# uDJV_board_2_v1_1.net
KiCad netlist of a schematic drawn in EAGLE
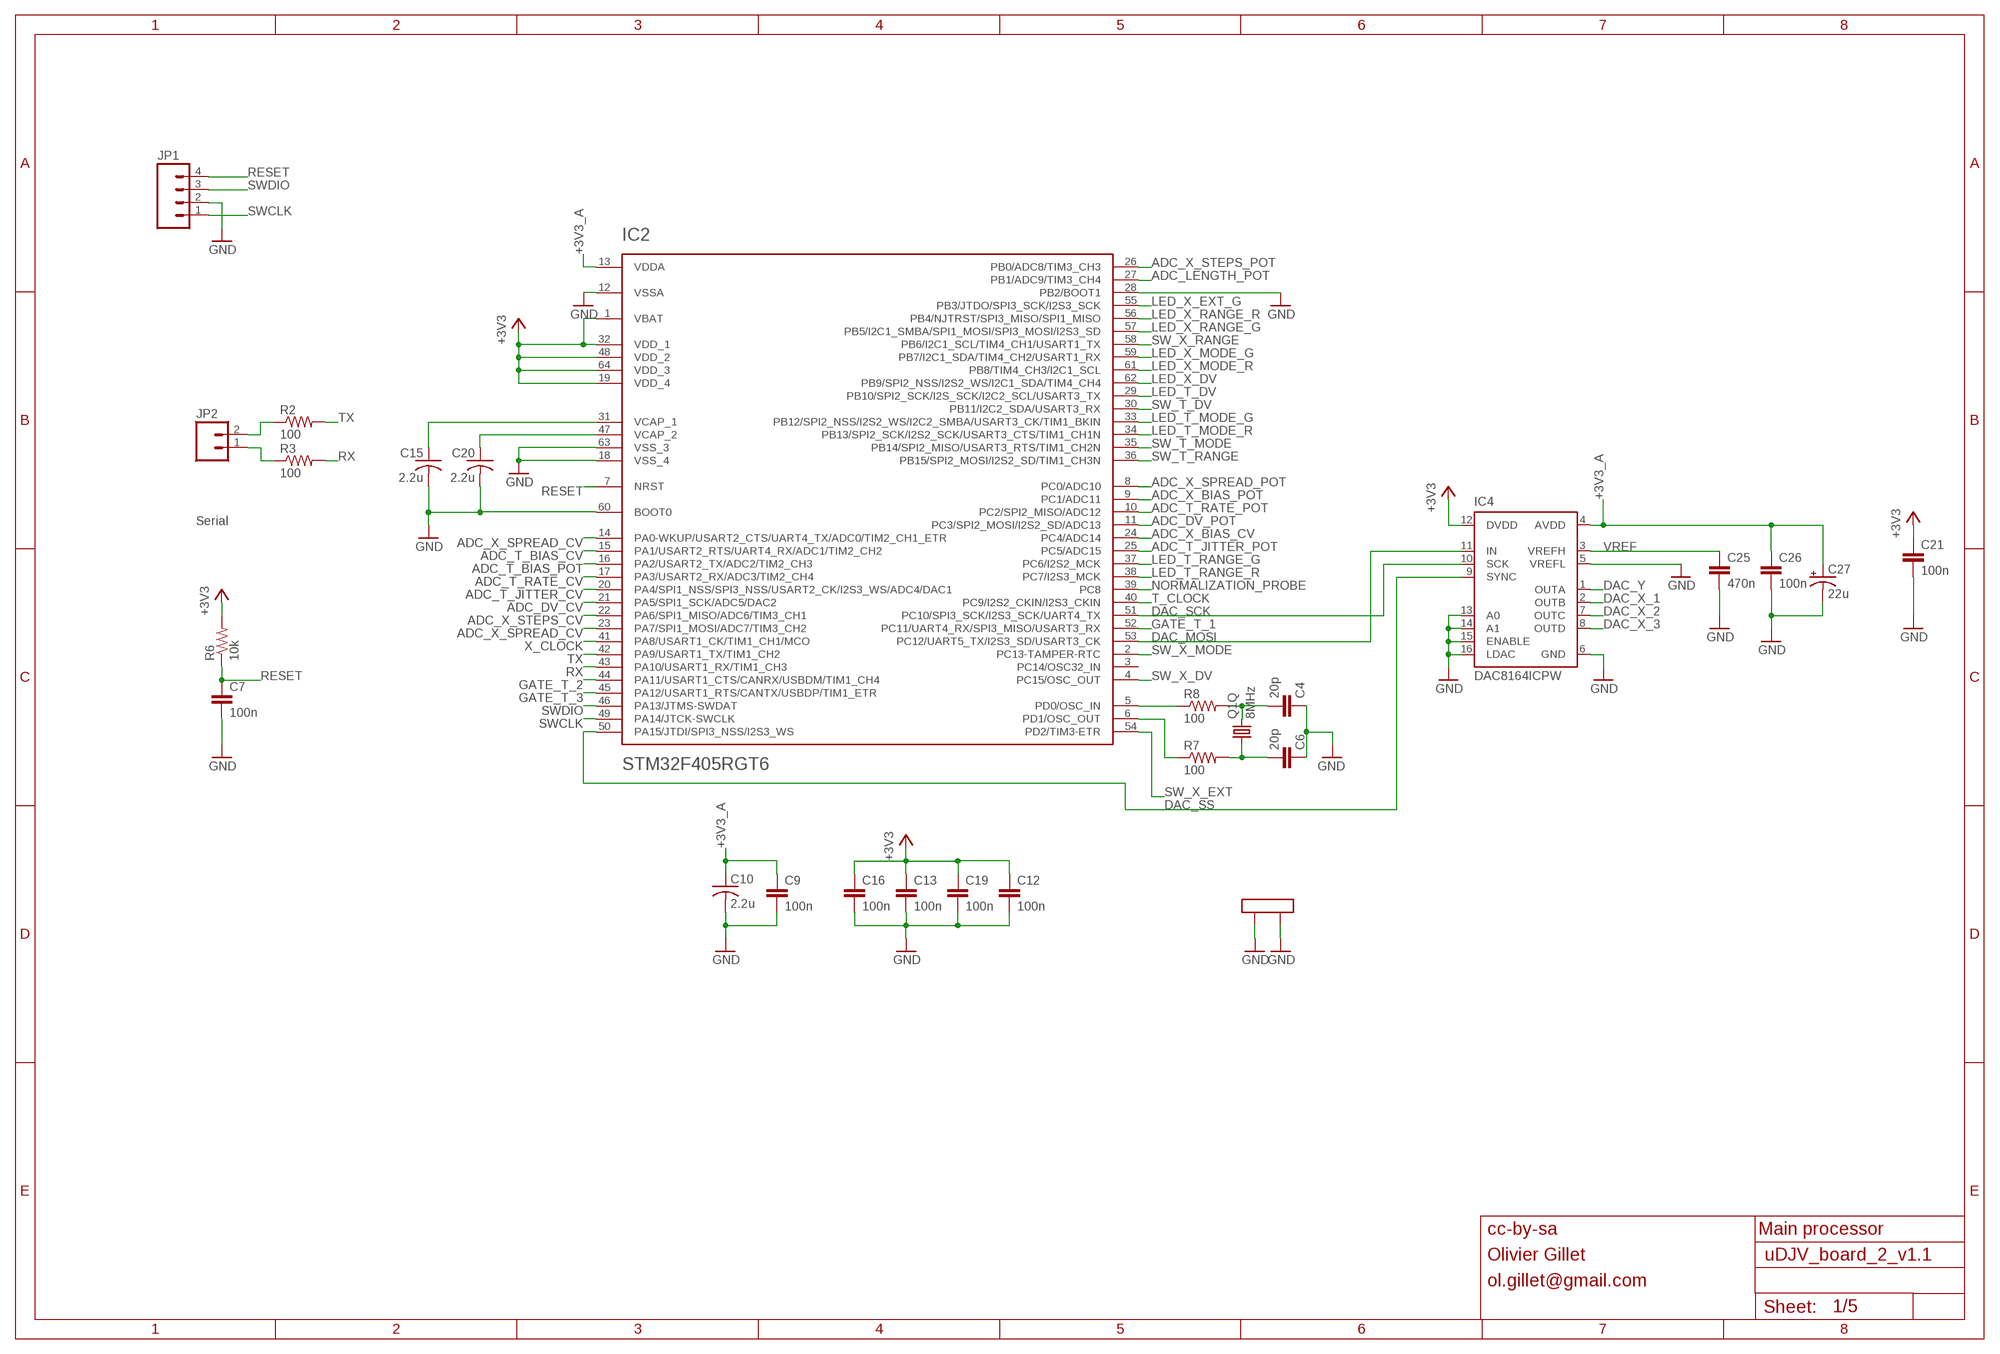
[diagram p0: schematic, sheet 1]
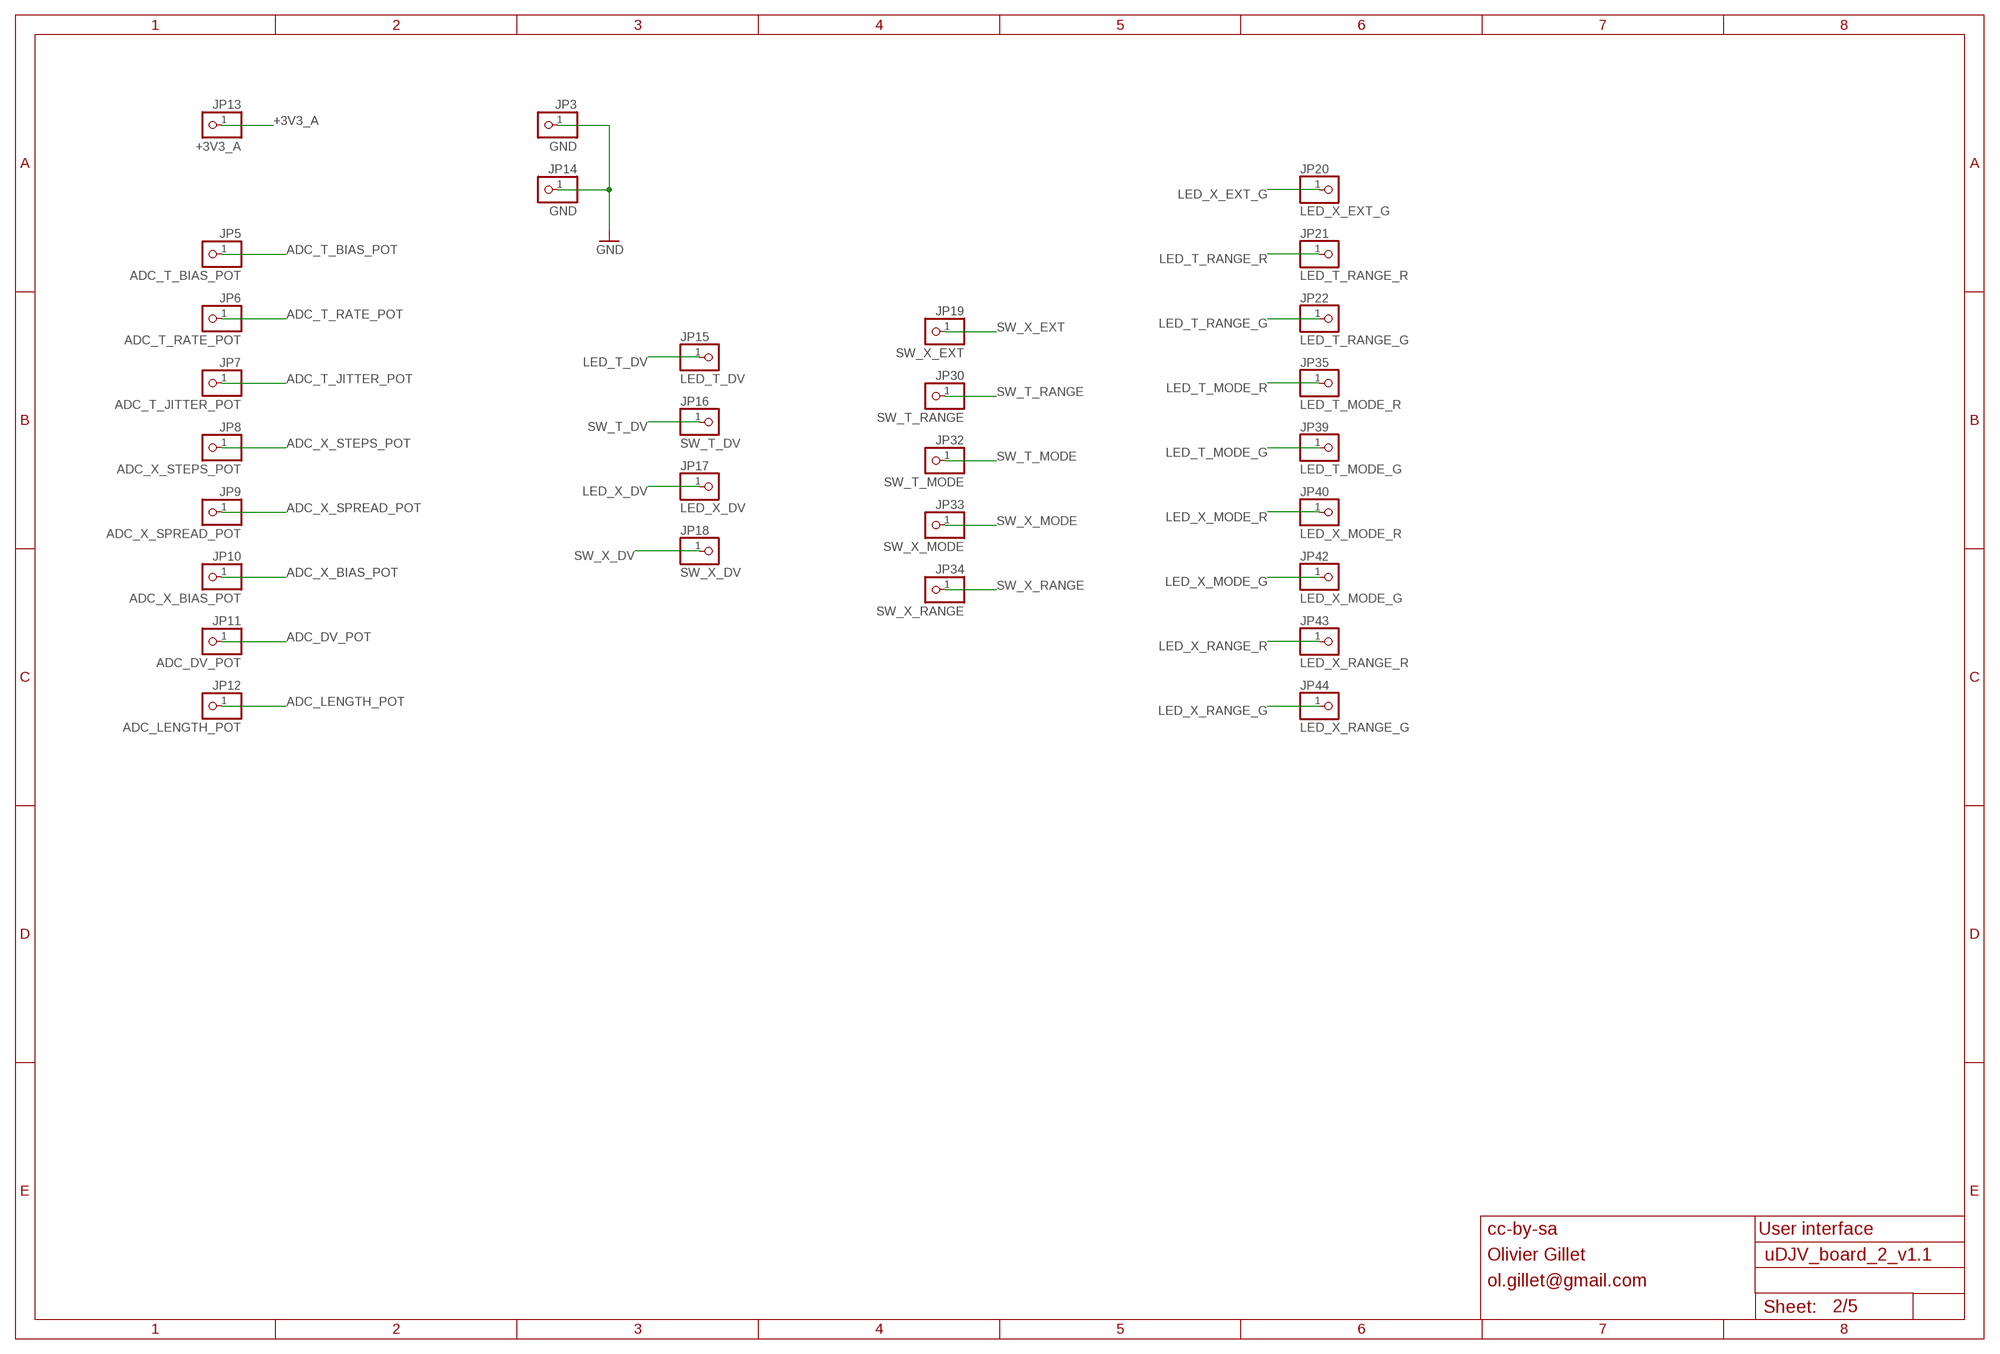
[diagram p1: schematic, sheet 2]
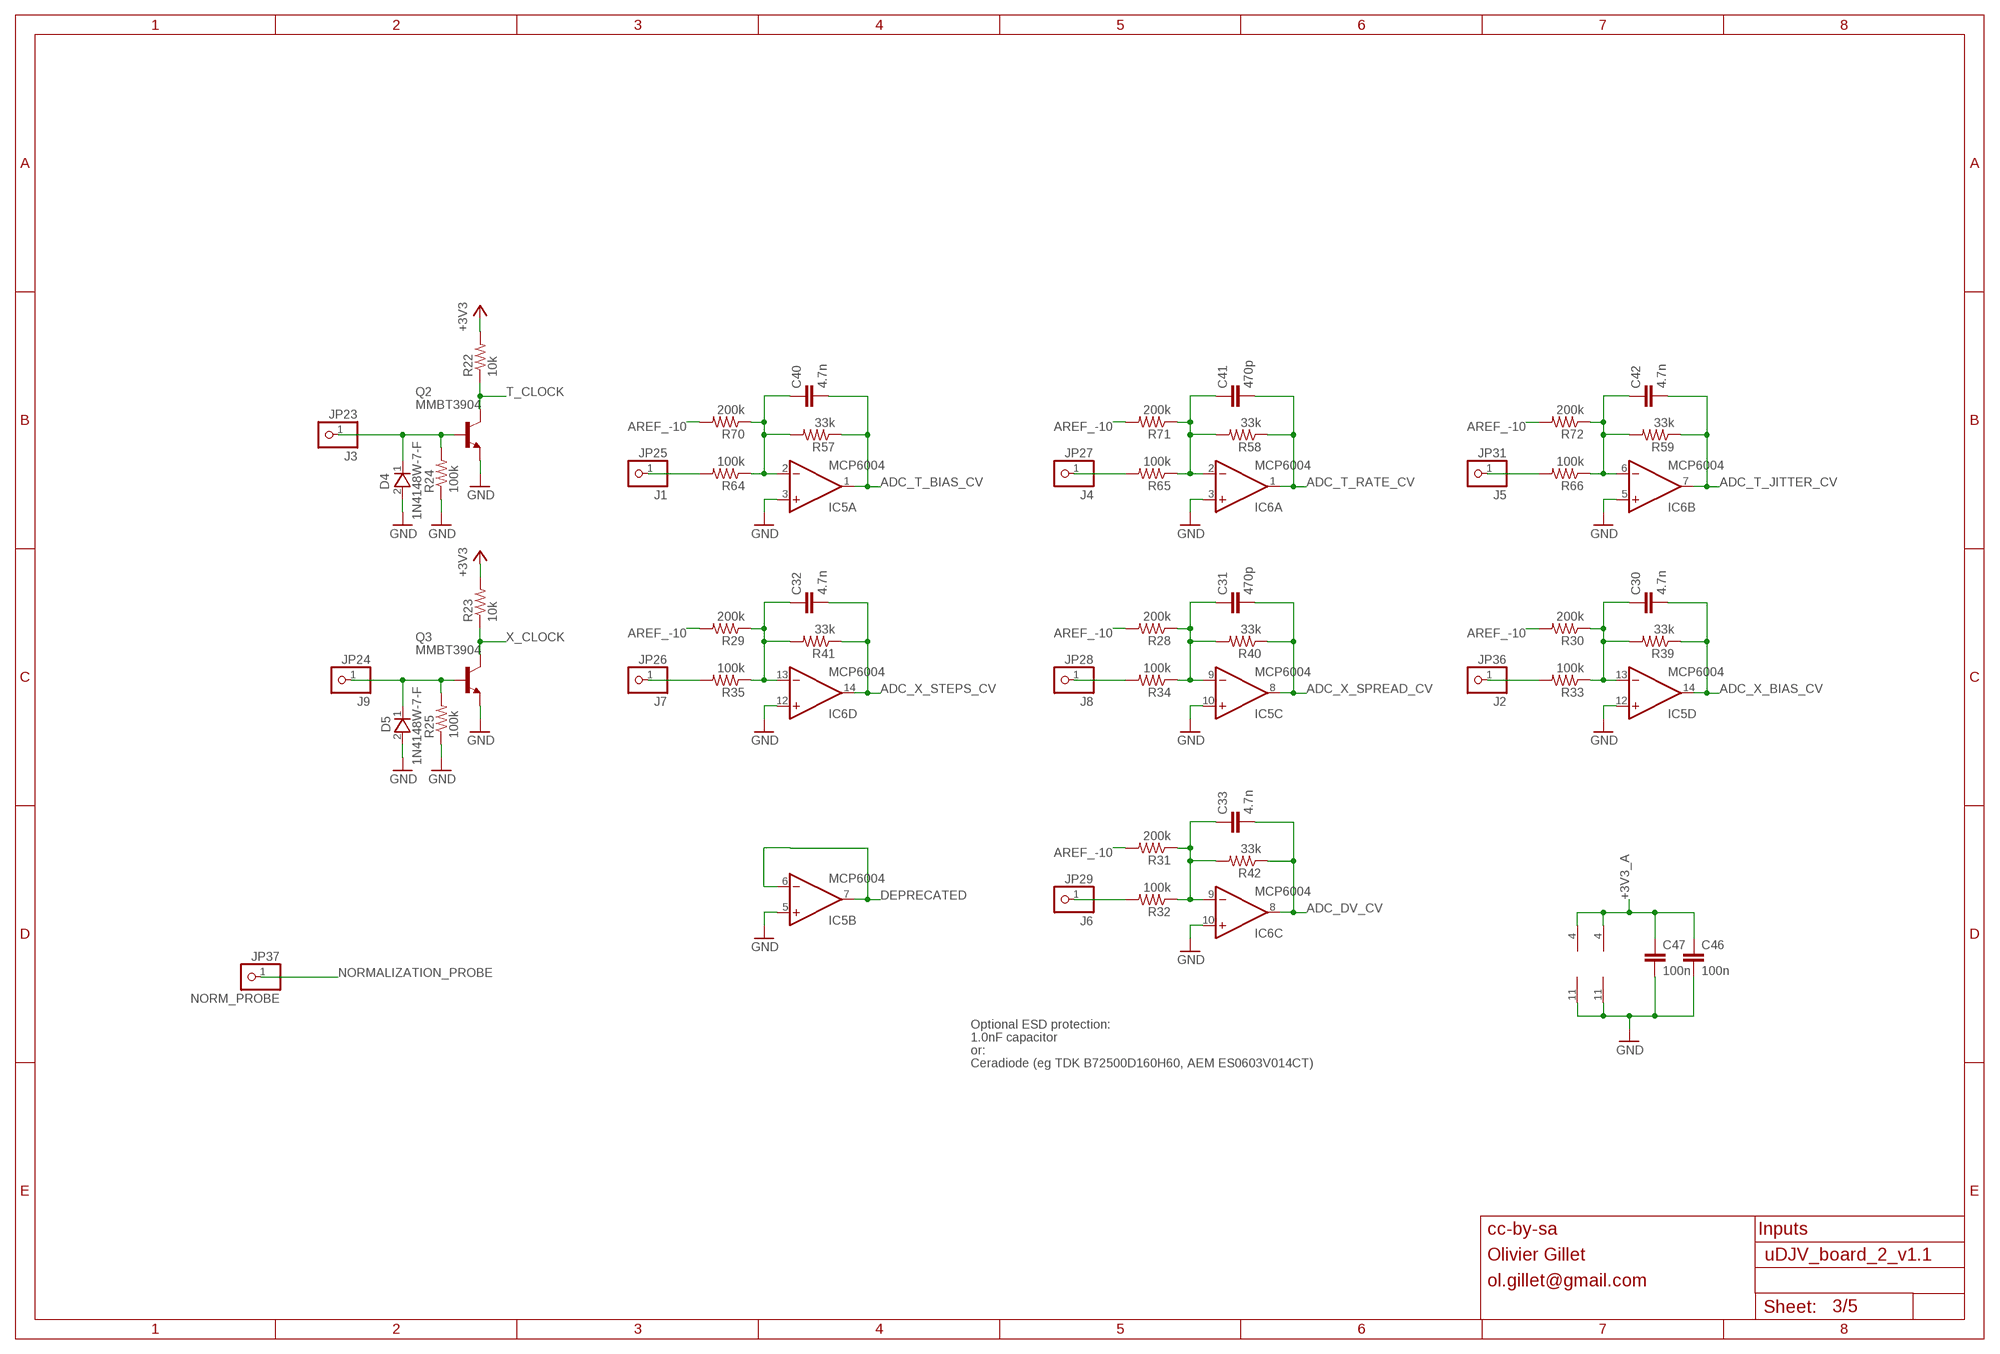
[diagram p2: schematic, sheet 3]
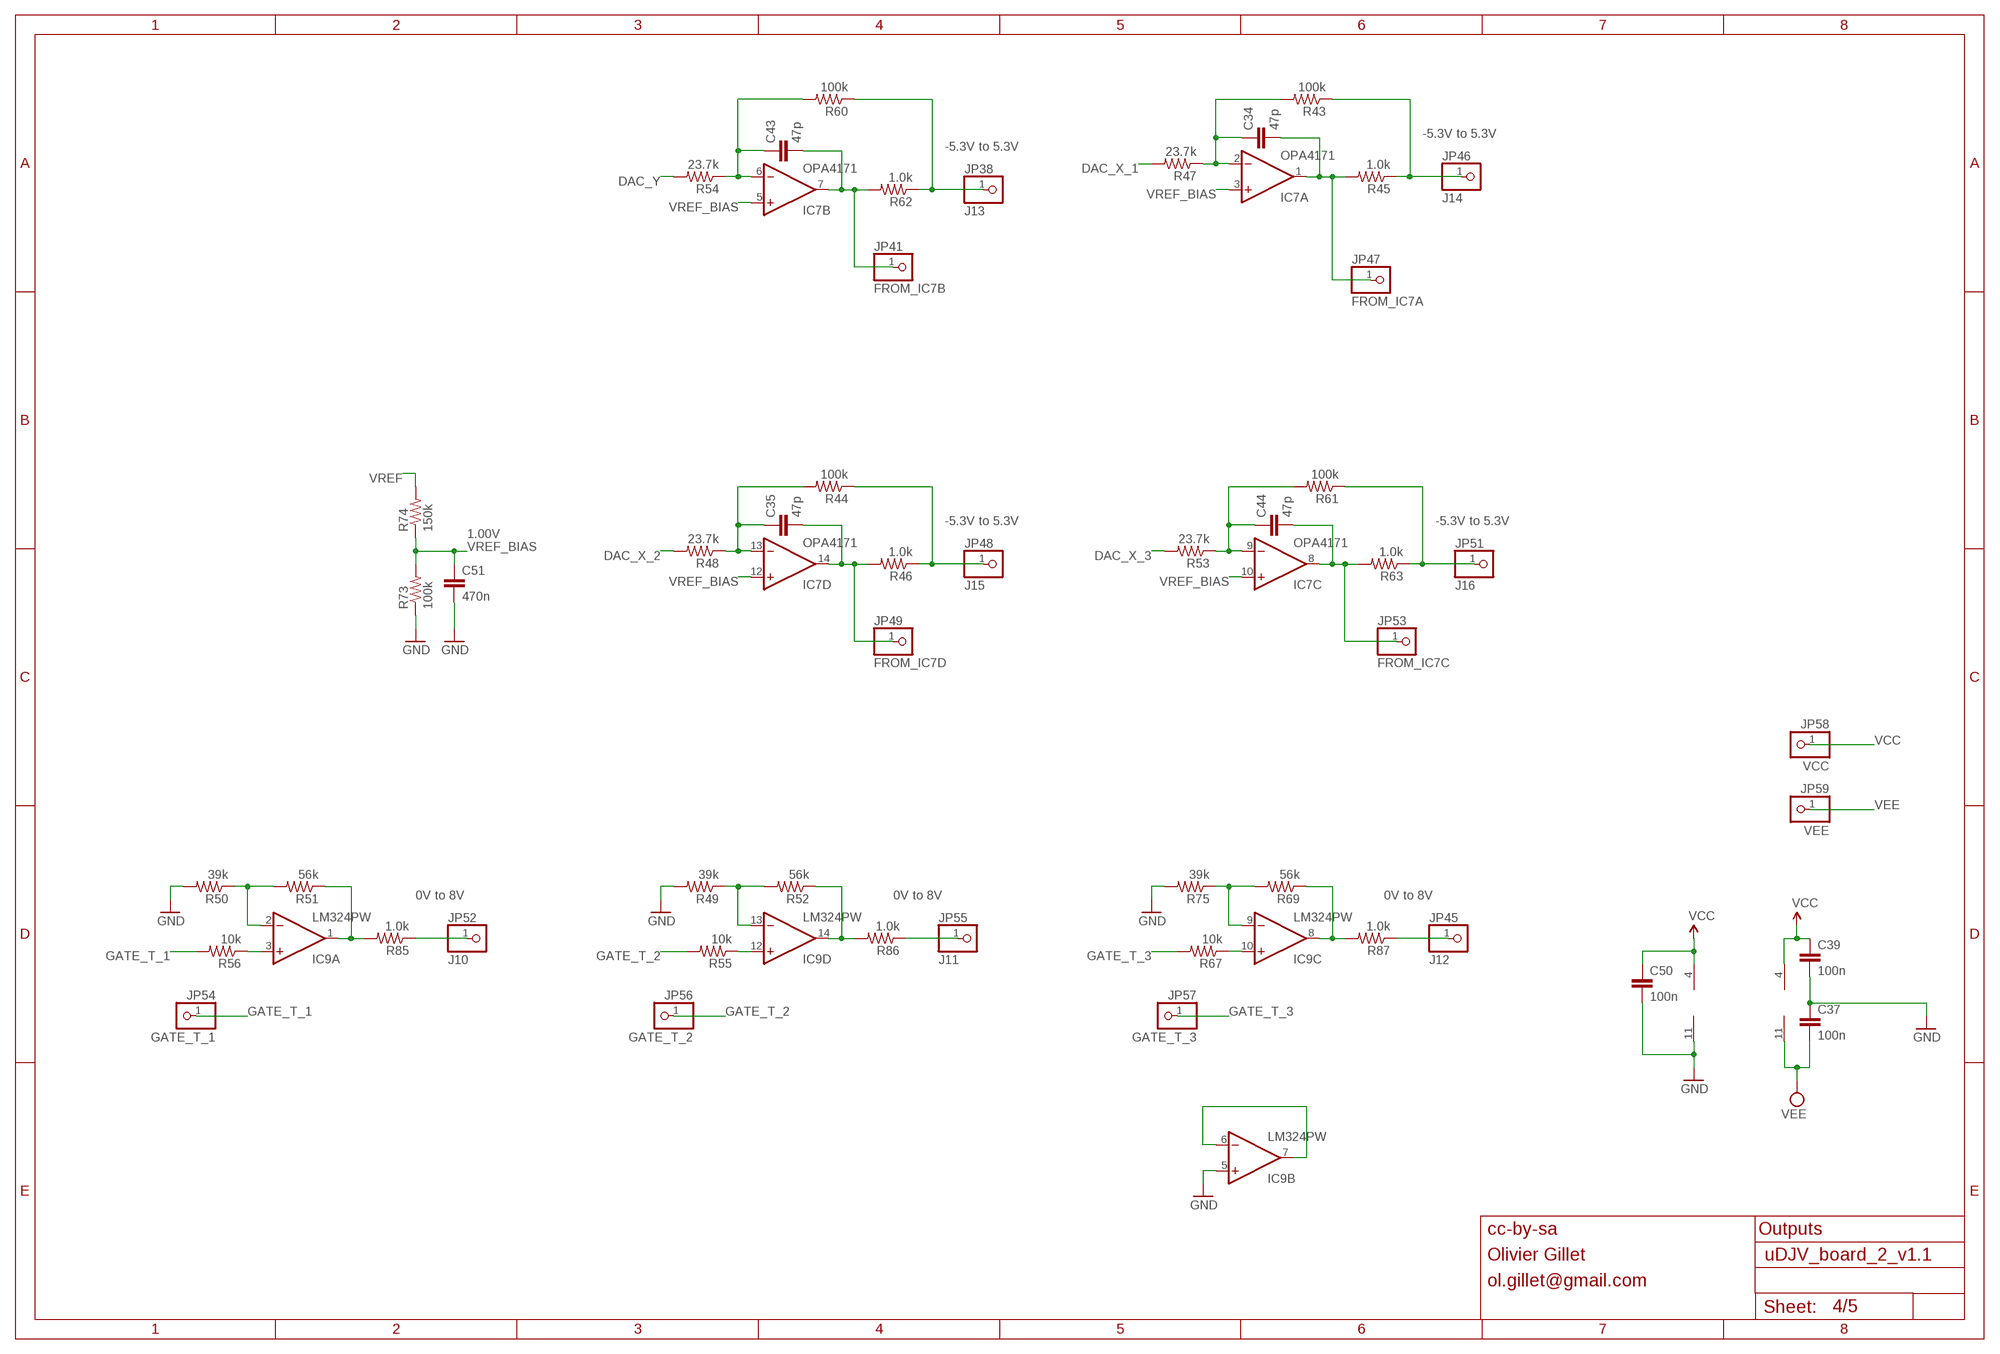
[diagram p3: schematic, sheet 4]
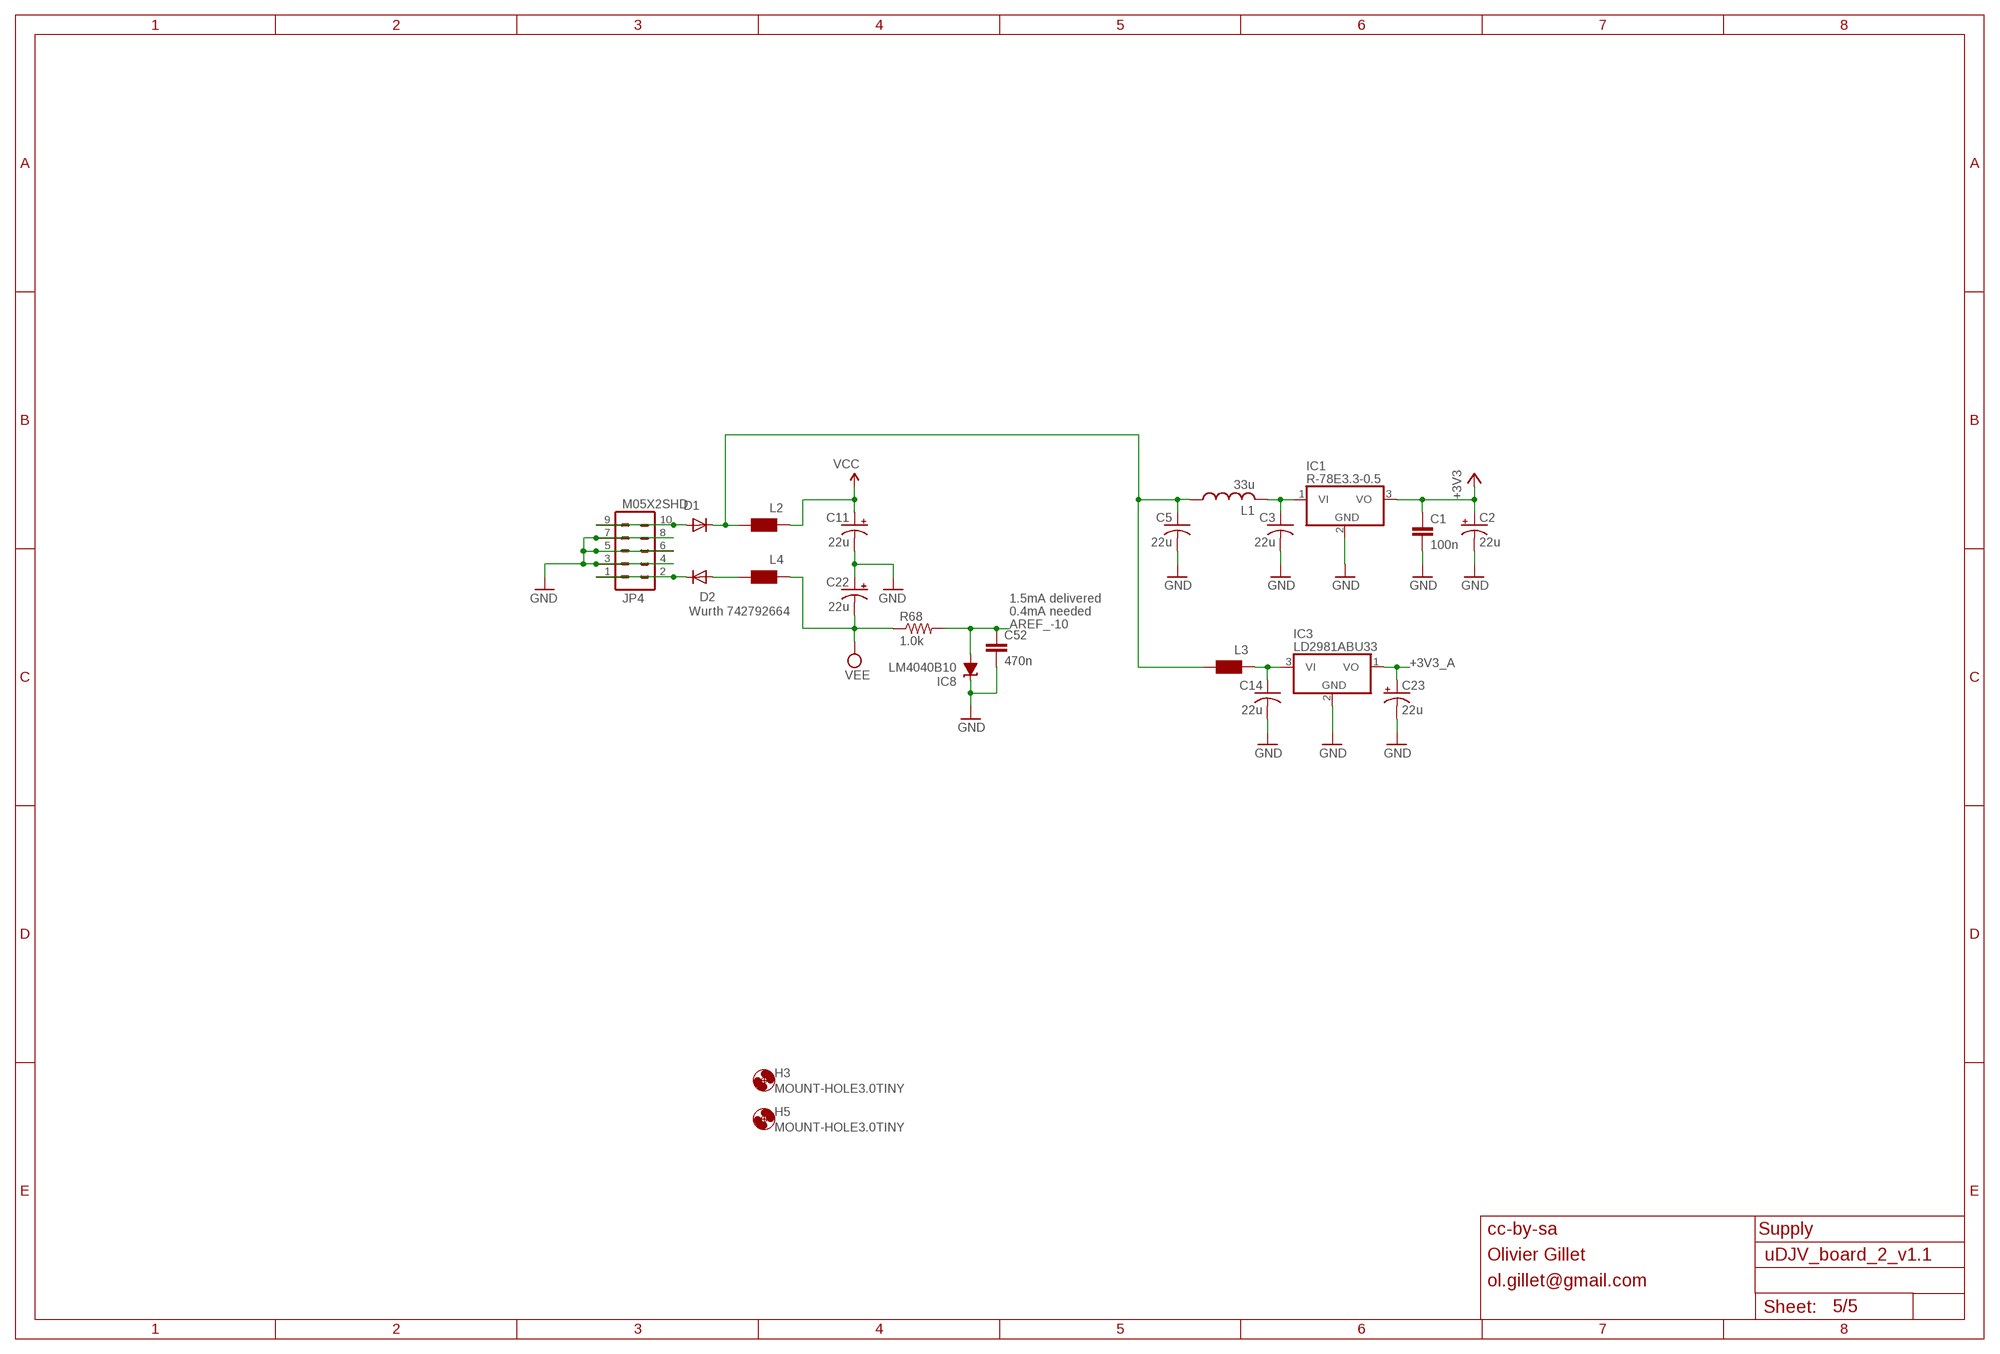
[diagram p4: schematic, sheet 5]

(export (version "E")
  (design (tool "Eeschema 10.0.6"))
  (components
    (comp (ref "C30")
      (value "4.7n")
      (footprint "eagle-import:PARTS_AMAN_RESISTOR_0603")
      (libsource (lib "eagle-import") (part "PARTS_AMAN_CAPACITOR"))
    )
    (comp (ref "C31")
      (value "470p")
      (footprint "eagle-import:PARTS_AMAN_RESISTOR_0603")
      (libsource (lib "eagle-import") (part "PARTS_AMAN_CAPACITOR"))
    )
    (comp (ref "C32")
      (value "4.7n")
      (footprint "eagle-import:PARTS_AMAN_RESISTOR_0603")
      (libsource (lib "eagle-import") (part "PARTS_AMAN_CAPACITOR"))
    )
    (comp (ref "C33")
      (value "4.7n")
      (footprint "eagle-import:PARTS_AMAN_RESISTOR_0603")
      (libsource (lib "eagle-import") (part "PARTS_AMAN_CAPACITOR"))
    )
    (comp (ref "C40")
      (value "4.7n")
      (footprint "eagle-import:PARTS_AMAN_RESISTOR_0603")
      (libsource (lib "eagle-import") (part "PARTS_AMAN_CAPACITOR"))
    )
    (comp (ref "C41")
      (value "470p")
      (footprint "eagle-import:PARTS_AMAN_RESISTOR_0603")
      (libsource (lib "eagle-import") (part "PARTS_AMAN_CAPACITOR"))
    )
    (comp (ref "C42")
      (value "4.7n")
      (footprint "eagle-import:PARTS_AMAN_RESISTOR_0603")
      (libsource (lib "eagle-import") (part "PARTS_AMAN_CAPACITOR"))
    )
    (comp (ref "C46")
      (value "100n")
      (footprint "eagle-import:PARTS_AMAN_RESISTOR_0603")
      (libsource (lib "eagle-import") (part "PARTS_AMAN_CAPACITOR"))
    )
    (comp (ref "C47")
      (value "100n")
      (footprint "eagle-import:PARTS_AMAN_RESISTOR_0603")
      (libsource (lib "eagle-import") (part "PARTS_AMAN_CAPACITOR"))
    )
    (comp (ref "D4")
      (value "1N4148W-7-F")
      (footprint "eagle-import:SOD3716X115N")
      (fields (field (name "MOUSER_PART_NUMBER") "621-1N4148W-F") (field (name "RS_PART_NUMBER") "7384728P"))
      (libsource (lib "eagle-import") (part "1N4148W-7-F"))
    )
    (comp (ref "D5")
      (value "1N4148W-7-F")
      (footprint "eagle-import:SOD3716X115N")
      (fields (field (name "MOUSER_PART_NUMBER") "621-1N4148W-F") (field (name "RS_PART_NUMBER") "7384728P"))
      (libsource (lib "eagle-import") (part "1N4148W-7-F"))
    )
    (comp (ref "IC5")
      (value "MCP6004")
      (footprint "eagle-import:TSSOP14_065")
      (libsource (lib "eagle-import") (part "TL074PW"))
    )
    (comp (ref "IC6")
      (value "MCP6004")
      (footprint "eagle-import:TSSOP14_065")
      (libsource (lib "eagle-import") (part "TL074PW"))
    )
    (comp (ref "JP23")
      (value "J3")
      (footprint "eagle-import:PARTS_AMAN_1X01")
      (libsource (lib "eagle-import") (part "PARTS_AMAN_PINHD-1X1"))
    )
    (comp (ref "JP24")
      (value "J9")
      (footprint "eagle-import:PARTS_AMAN_1X01")
      (libsource (lib "eagle-import") (part "PARTS_AMAN_PINHD-1X1"))
    )
    (comp (ref "JP25")
      (value "J1")
      (footprint "eagle-import:PARTS_AMAN_1X01")
      (libsource (lib "eagle-import") (part "PARTS_AMAN_PINHD-1X1"))
    )
    (comp (ref "JP26")
      (value "J7")
      (footprint "eagle-import:PARTS_AMAN_1X01")
      (libsource (lib "eagle-import") (part "PARTS_AMAN_PINHD-1X1"))
    )
    (comp (ref "JP27")
      (value "J4")
      (footprint "eagle-import:PARTS_AMAN_1X01")
      (libsource (lib "eagle-import") (part "PARTS_AMAN_PINHD-1X1"))
    )
    (comp (ref "JP28")
      (value "J8")
      (footprint "eagle-import:PARTS_AMAN_1X01")
      (libsource (lib "eagle-import") (part "PARTS_AMAN_PINHD-1X1"))
    )
    (comp (ref "JP29")
      (value "J6")
      (footprint "eagle-import:PARTS_AMAN_1X01")
      (libsource (lib "eagle-import") (part "PARTS_AMAN_PINHD-1X1"))
    )
    (comp (ref "JP31")
      (value "J5")
      (footprint "eagle-import:PARTS_AMAN_1X01")
      (libsource (lib "eagle-import") (part "PARTS_AMAN_PINHD-1X1"))
    )
    (comp (ref "JP36")
      (value "J2")
      (footprint "eagle-import:PARTS_AMAN_1X01")
      (libsource (lib "eagle-import") (part "PARTS_AMAN_PINHD-1X1"))
    )
    (comp (ref "JP37")
      (value "NORM_PROBE")
      (footprint "eagle-import:PARTS_AMAN_1X01")
      (libsource (lib "eagle-import") (part "PARTS_AMAN_PINHD-1X1"))
    )
    (comp (ref "Q2")
      (value "MMBT3904")
      (footprint "eagle-import:SOT23-BEC")
      (libsource (lib "eagle-import") (part "-NPN-SOT23-BECMMBT3904LT1"))
    )
    (comp (ref "Q3")
      (value "MMBT3904")
      (footprint "eagle-import:SOT23-BEC")
      (libsource (lib "eagle-import") (part "-NPN-SOT23-BECMMBT3904LT1"))
    )
    (comp (ref "R22")
      (value "10k")
      (footprint "eagle-import:PARTS_AMAN_RESISTOR_0603")
      (libsource (lib "eagle-import") (part "PARTS_AMAN_RESISTOR"))
    )
    (comp (ref "R23")
      (value "10k")
      (footprint "eagle-import:PARTS_AMAN_RESISTOR_0603")
      (libsource (lib "eagle-import") (part "PARTS_AMAN_RESISTOR"))
    )
    (comp (ref "R24")
      (value "100k")
      (footprint "eagle-import:PARTS_AMAN_RESISTOR_0603")
      (libsource (lib "eagle-import") (part "PARTS_AMAN_RESISTOR"))
    )
    (comp (ref "R25")
      (value "100k")
      (footprint "eagle-import:PARTS_AMAN_RESISTOR_0603")
      (libsource (lib "eagle-import") (part "PARTS_AMAN_RESISTOR"))
    )
    (comp (ref "R28")
      (value "200k")
      (footprint "eagle-import:PARTS_AMAN_RESISTOR_0603")
      (libsource (lib "eagle-import") (part "PARTS_AMAN_RESISTOR"))
    )
    (comp (ref "R29")
      (value "200k")
      (footprint "eagle-import:PARTS_AMAN_RESISTOR_0603")
      (libsource (lib "eagle-import") (part "PARTS_AMAN_RESISTOR"))
    )
    (comp (ref "R30")
      (value "200k")
      (footprint "eagle-import:PARTS_AMAN_RESISTOR_0603")
      (libsource (lib "eagle-import") (part "PARTS_AMAN_RESISTOR"))
    )
    (comp (ref "R31")
      (value "200k")
      (footprint "eagle-import:PARTS_AMAN_RESISTOR_0603")
      (libsource (lib "eagle-import") (part "PARTS_AMAN_RESISTOR"))
    )
    (comp (ref "R32")
      (value "100k")
      (footprint "eagle-import:PARTS_AMAN_RESISTOR_0603")
      (libsource (lib "eagle-import") (part "PARTS_AMAN_RESISTOR"))
    )
    (comp (ref "R33")
      (value "100k")
      (footprint "eagle-import:PARTS_AMAN_RESISTOR_0603")
      (libsource (lib "eagle-import") (part "PARTS_AMAN_RESISTOR"))
    )
    (comp (ref "R34")
      (value "100k")
      (footprint "eagle-import:PARTS_AMAN_RESISTOR_0603")
      (libsource (lib "eagle-import") (part "PARTS_AMAN_RESISTOR"))
    )
    (comp (ref "R35")
      (value "100k")
      (footprint "eagle-import:PARTS_AMAN_RESISTOR_0603")
      (libsource (lib "eagle-import") (part "PARTS_AMAN_RESISTOR"))
    )
    (comp (ref "R39")
      (value "33k")
      (footprint "eagle-import:PARTS_AMAN_RESISTOR_0603")
      (libsource (lib "eagle-import") (part "PARTS_AMAN_RESISTOR"))
    )
    (comp (ref "R40")
      (value "33k")
      (footprint "eagle-import:PARTS_AMAN_RESISTOR_0603")
      (libsource (lib "eagle-import") (part "PARTS_AMAN_RESISTOR"))
    )
    (comp (ref "R41")
      (value "33k")
      (footprint "eagle-import:PARTS_AMAN_RESISTOR_0603")
      (libsource (lib "eagle-import") (part "PARTS_AMAN_RESISTOR"))
    )
    (comp (ref "R42")
      (value "33k")
      (footprint "eagle-import:PARTS_AMAN_RESISTOR_0603")
      (libsource (lib "eagle-import") (part "PARTS_AMAN_RESISTOR"))
    )
    (comp (ref "R57")
      (value "33k")
      (footprint "eagle-import:PARTS_AMAN_RESISTOR_0603")
      (libsource (lib "eagle-import") (part "PARTS_AMAN_RESISTOR"))
    )
    (comp (ref "R58")
      (value "33k")
      (footprint "eagle-import:PARTS_AMAN_RESISTOR_0603")
      (libsource (lib "eagle-import") (part "PARTS_AMAN_RESISTOR"))
    )
    (comp (ref "R59")
      (value "33k")
      (footprint "eagle-import:PARTS_AMAN_RESISTOR_0603")
      (libsource (lib "eagle-import") (part "PARTS_AMAN_RESISTOR"))
    )
    (comp (ref "R64")
      (value "100k")
      (footprint "eagle-import:PARTS_AMAN_RESISTOR_0603")
      (libsource (lib "eagle-import") (part "PARTS_AMAN_RESISTOR"))
    )
    (comp (ref "R65")
      (value "100k")
      (footprint "eagle-import:PARTS_AMAN_RESISTOR_0603")
      (libsource (lib "eagle-import") (part "PARTS_AMAN_RESISTOR"))
    )
    (comp (ref "R66")
      (value "100k")
      (footprint "eagle-import:PARTS_AMAN_RESISTOR_0603")
      (libsource (lib "eagle-import") (part "PARTS_AMAN_RESISTOR"))
    )
    (comp (ref "R70")
      (value "200k")
      (footprint "eagle-import:PARTS_AMAN_RESISTOR_0603")
      (libsource (lib "eagle-import") (part "PARTS_AMAN_RESISTOR"))
    )
    (comp (ref "R71")
      (value "200k")
      (footprint "eagle-import:PARTS_AMAN_RESISTOR_0603")
      (libsource (lib "eagle-import") (part "PARTS_AMAN_RESISTOR"))
    )
    (comp (ref "R72")
      (value "200k")
      (footprint "eagle-import:PARTS_AMAN_RESISTOR_0603")
      (libsource (lib "eagle-import") (part "PARTS_AMAN_RESISTOR"))
    )
    (comp (ref "C34")
      (value "47p")
      (footprint "eagle-import:PARTS_AMAN_RESISTOR_0603")
      (libsource (lib "eagle-import") (part "PARTS_AMAN_CAPACITOR"))
    )
    (comp (ref "C35")
      (value "47p")
      (footprint "eagle-import:PARTS_AMAN_RESISTOR_0603")
      (libsource (lib "eagle-import") (part "PARTS_AMAN_CAPACITOR"))
    )
    (comp (ref "C37")
      (value "100n")
      (footprint "eagle-import:PARTS_AMAN_RESISTOR_0603")
      (libsource (lib "eagle-import") (part "PARTS_AMAN_CAPACITOR"))
    )
    (comp (ref "C39")
      (value "100n")
      (footprint "eagle-import:PARTS_AMAN_RESISTOR_0603")
      (libsource (lib "eagle-import") (part "PARTS_AMAN_CAPACITOR"))
    )
    (comp (ref "C43")
      (value "47p")
      (footprint "eagle-import:PARTS_AMAN_RESISTOR_0603")
      (libsource (lib "eagle-import") (part "PARTS_AMAN_CAPACITOR"))
    )
    (comp (ref "C44")
      (value "47p")
      (footprint "eagle-import:PARTS_AMAN_RESISTOR_0603")
      (libsource (lib "eagle-import") (part "PARTS_AMAN_CAPACITOR"))
    )
    (comp (ref "C50")
      (value "100n")
      (footprint "eagle-import:PARTS_AMAN_RESISTOR_0603")
      (libsource (lib "eagle-import") (part "PARTS_AMAN_CAPACITOR"))
    )
    (comp (ref "C51")
      (value "470n")
      (footprint "eagle-import:PARTS_AMAN_RESISTOR_0603")
      (libsource (lib "eagle-import") (part "PARTS_AMAN_CAPACITOR"))
    )
    (comp (ref "IC7")
      (value "OPA4171")
      (footprint "eagle-import:TSSOP14_065")
      (libsource (lib "eagle-import") (part "TL074PW"))
    )
    (comp (ref "IC9")
      (value "LM324PW")
      (footprint "eagle-import:TSSOP14_065")
      (libsource (lib "eagle-import") (part "TL074PW"))
    )
    (comp (ref "JP38")
      (value "J13")
      (footprint "eagle-import:PARTS_AMAN_1X01")
      (libsource (lib "eagle-import") (part "PARTS_AMAN_PINHD-1X1"))
    )
    (comp (ref "JP41")
      (value "FROM_IC7B")
      (footprint "eagle-import:PARTS_AMAN_1X01")
      (libsource (lib "eagle-import") (part "PARTS_AMAN_PINHD-1X1"))
    )
    (comp (ref "JP45")
      (value "J12")
      (footprint "eagle-import:PARTS_AMAN_1X01")
      (libsource (lib "eagle-import") (part "PARTS_AMAN_PINHD-1X1"))
    )
    (comp (ref "JP46")
      (value "J14")
      (footprint "eagle-import:PARTS_AMAN_1X01")
      (libsource (lib "eagle-import") (part "PARTS_AMAN_PINHD-1X1"))
    )
    (comp (ref "JP47")
      (value "FROM_IC7A")
      (footprint "eagle-import:PARTS_AMAN_1X01")
      (libsource (lib "eagle-import") (part "PARTS_AMAN_PINHD-1X1"))
    )
    (comp (ref "JP48")
      (value "J15")
      (footprint "eagle-import:PARTS_AMAN_1X01")
      (libsource (lib "eagle-import") (part "PARTS_AMAN_PINHD-1X1"))
    )
    (comp (ref "JP49")
      (value "FROM_IC7D")
      (footprint "eagle-import:PARTS_AMAN_1X01")
      (libsource (lib "eagle-import") (part "PARTS_AMAN_PINHD-1X1"))
    )
    (comp (ref "JP51")
      (value "J16")
      (footprint "eagle-import:PARTS_AMAN_1X01")
      (libsource (lib "eagle-import") (part "PARTS_AMAN_PINHD-1X1"))
    )
    (comp (ref "JP52")
      (value "J10")
      (footprint "eagle-import:PARTS_AMAN_1X01")
      (libsource (lib "eagle-import") (part "PARTS_AMAN_PINHD-1X1"))
    )
    (comp (ref "JP53")
      (value "FROM_IC7C")
      (footprint "eagle-import:PARTS_AMAN_1X01")
      (libsource (lib "eagle-import") (part "PARTS_AMAN_PINHD-1X1"))
    )
    (comp (ref "JP54")
      (value "GATE_T_1")
      (footprint "eagle-import:PARTS_AMAN_1X01")
      (libsource (lib "eagle-import") (part "PARTS_AMAN_PINHD-1X1"))
    )
    (comp (ref "JP55")
      (value "J11")
      (footprint "eagle-import:PARTS_AMAN_1X01")
      (libsource (lib "eagle-import") (part "PARTS_AMAN_PINHD-1X1"))
    )
    (comp (ref "JP56")
      (value "GATE_T_2")
      (footprint "eagle-import:PARTS_AMAN_1X01")
      (libsource (lib "eagle-import") (part "PARTS_AMAN_PINHD-1X1"))
    )
    (comp (ref "JP57")
      (value "GATE_T_3")
      (footprint "eagle-import:PARTS_AMAN_1X01")
      (libsource (lib "eagle-import") (part "PARTS_AMAN_PINHD-1X1"))
    )
    (comp (ref "JP58")
      (value "VCC")
      (footprint "eagle-import:PARTS_AMAN_1X01")
      (libsource (lib "eagle-import") (part "PARTS_AMAN_PINHD-1X1"))
    )
    (comp (ref "JP59")
      (value "VEE")
      (footprint "eagle-import:PARTS_AMAN_1X01")
      (libsource (lib "eagle-import") (part "PARTS_AMAN_PINHD-1X1"))
    )
    (comp (ref "R43")
      (value "100k")
      (footprint "eagle-import:PARTS_AMAN_RESISTOR_0603")
      (libsource (lib "eagle-import") (part "PARTS_AMAN_RESISTOR"))
    )
    (comp (ref "R44")
      (value "100k")
      (footprint "eagle-import:PARTS_AMAN_RESISTOR_0603")
      (libsource (lib "eagle-import") (part "PARTS_AMAN_RESISTOR"))
    )
    (comp (ref "R45")
      (value "1.0k")
      (footprint "eagle-import:PARTS_AMAN_RESISTOR_0603")
      (libsource (lib "eagle-import") (part "PARTS_AMAN_RESISTOR"))
    )
    (comp (ref "R46")
      (value "1.0k")
      (footprint "eagle-import:R0603")
      (libsource (lib "eagle-import") (part "R-US_R0603"))
    )
    (comp (ref "R47")
      (value "23.7k")
      (footprint "eagle-import:PARTS_AMAN_RESISTOR_0603")
      (libsource (lib "eagle-import") (part "PARTS_AMAN_RESISTOR"))
    )
    (comp (ref "R48")
      (value "23.7k")
      (footprint "eagle-import:PARTS_AMAN_RESISTOR_0603")
      (libsource (lib "eagle-import") (part "PARTS_AMAN_RESISTOR"))
    )
    (comp (ref "R49")
      (value "39k")
      (footprint "eagle-import:PARTS_AMAN_RESISTOR_0603")
      (libsource (lib "eagle-import") (part "PARTS_AMAN_RESISTOR"))
    )
    (comp (ref "R50")
      (value "39k")
      (footprint "eagle-import:PARTS_AMAN_RESISTOR_0603")
      (libsource (lib "eagle-import") (part "PARTS_AMAN_RESISTOR"))
    )
    (comp (ref "R51")
      (value "56k")
      (footprint "eagle-import:PARTS_AMAN_RESISTOR_0603")
      (libsource (lib "eagle-import") (part "PARTS_AMAN_RESISTOR"))
    )
    (comp (ref "R52")
      (value "56k")
      (footprint "eagle-import:PARTS_AMAN_RESISTOR_0603")
      (libsource (lib "eagle-import") (part "PARTS_AMAN_RESISTOR"))
    )
    (comp (ref "R53")
      (value "23.7k")
      (footprint "eagle-import:PARTS_AMAN_RESISTOR_0603")
      (libsource (lib "eagle-import") (part "PARTS_AMAN_RESISTOR"))
    )
    (comp (ref "R54")
      (value "23.7k")
      (footprint "eagle-import:PARTS_AMAN_RESISTOR_0603")
      (libsource (lib "eagle-import") (part "PARTS_AMAN_RESISTOR"))
    )
    (comp (ref "R55")
      (value "10k")
      (footprint "eagle-import:PARTS_AMAN_RESISTOR_0603")
      (libsource (lib "eagle-import") (part "PARTS_AMAN_RESISTOR"))
    )
    (comp (ref "R56")
      (value "10k")
      (footprint "eagle-import:PARTS_AMAN_RESISTOR_0603")
      (libsource (lib "eagle-import") (part "PARTS_AMAN_RESISTOR"))
    )
    (comp (ref "R60")
      (value "100k")
      (footprint "eagle-import:PARTS_AMAN_RESISTOR_0603")
      (libsource (lib "eagle-import") (part "PARTS_AMAN_RESISTOR"))
    )
    (comp (ref "R61")
      (value "100k")
      (footprint "eagle-import:PARTS_AMAN_RESISTOR_0603")
      (libsource (lib "eagle-import") (part "PARTS_AMAN_RESISTOR"))
    )
    (comp (ref "R62")
      (value "1.0k")
      (footprint "eagle-import:R0603")
      (libsource (lib "eagle-import") (part "R-US_R0603"))
    )
    (comp (ref "R63")
      (value "1.0k")
      (footprint "eagle-import:R0603")
      (libsource (lib "eagle-import") (part "R-US_R0603"))
    )
    (comp (ref "R67")
      (value "10k")
      (footprint "eagle-import:PARTS_AMAN_RESISTOR_0603")
      (libsource (lib "eagle-import") (part "PARTS_AMAN_RESISTOR"))
    )
    (comp (ref "R69")
      (value "56k")
      (footprint "eagle-import:PARTS_AMAN_RESISTOR_0603")
      (libsource (lib "eagle-import") (part "PARTS_AMAN_RESISTOR"))
    )
    (comp (ref "R73")
      (value "100k")
      (footprint "eagle-import:PARTS_AMAN_RESISTOR_0603")
      (libsource (lib "eagle-import") (part "PARTS_AMAN_RESISTOR"))
    )
    (comp (ref "R74")
      (value "150k")
      (footprint "eagle-import:PARTS_AMAN_RESISTOR_0603")
      (libsource (lib "eagle-import") (part "PARTS_AMAN_RESISTOR"))
    )
    (comp (ref "R75")
      (value "39k")
      (footprint "eagle-import:PARTS_AMAN_RESISTOR_0603")
      (libsource (lib "eagle-import") (part "PARTS_AMAN_RESISTOR"))
    )
    (comp (ref "R85")
      (value "1.0k")
      (footprint "eagle-import:R0603")
      (libsource (lib "eagle-import") (part "R-US_R0603"))
    )
    (comp (ref "R86")
      (value "1.0k")
      (footprint "eagle-import:R0603")
      (libsource (lib "eagle-import") (part "R-US_R0603"))
    )
    (comp (ref "R87")
      (value "1.0k")
      (footprint "eagle-import:R0603")
      (libsource (lib "eagle-import") (part "R-US_R0603"))
    )
    (comp (ref "JP3")
      (value "GND")
      (footprint "eagle-import:PARTS_AMAN_1X01")
      (libsource (lib "eagle-import") (part "PARTS_AMAN_PINHD-1X1"))
    )
    (comp (ref "JP5")
      (value "ADC_T_BIAS_POT")
      (footprint "eagle-import:PARTS_AMAN_1X01")
      (libsource (lib "eagle-import") (part "PARTS_AMAN_PINHD-1X1"))
    )
    (comp (ref "JP6")
      (value "ADC_T_RATE_POT")
      (footprint "eagle-import:PARTS_AMAN_1X01")
      (libsource (lib "eagle-import") (part "PARTS_AMAN_PINHD-1X1"))
    )
    (comp (ref "JP7")
      (value "ADC_T_JITTER_POT")
      (footprint "eagle-import:PARTS_AMAN_1X01")
      (libsource (lib "eagle-import") (part "PARTS_AMAN_PINHD-1X1"))
    )
    (comp (ref "JP8")
      (value "ADC_X_STEPS_POT")
      (footprint "eagle-import:PARTS_AMAN_1X01")
      (libsource (lib "eagle-import") (part "PARTS_AMAN_PINHD-1X1"))
    )
    (comp (ref "JP9")
      (value "ADC_X_SPREAD_POT")
      (footprint "eagle-import:PARTS_AMAN_1X01")
      (libsource (lib "eagle-import") (part "PARTS_AMAN_PINHD-1X1"))
    )
    (comp (ref "JP10")
      (value "ADC_X_BIAS_POT")
      (footprint "eagle-import:PARTS_AMAN_1X01")
      (libsource (lib "eagle-import") (part "PARTS_AMAN_PINHD-1X1"))
    )
    (comp (ref "JP11")
      (value "ADC_DV_POT")
      (footprint "eagle-import:PARTS_AMAN_1X01")
      (libsource (lib "eagle-import") (part "PARTS_AMAN_PINHD-1X1"))
    )
    (comp (ref "JP12")
      (value "ADC_LENGTH_POT")
      (footprint "eagle-import:PARTS_AMAN_1X01")
      (libsource (lib "eagle-import") (part "PARTS_AMAN_PINHD-1X1"))
    )
    (comp (ref "JP13")
      (value "+3V3_A")
      (footprint "eagle-import:PARTS_AMAN_1X01")
      (libsource (lib "eagle-import") (part "PARTS_AMAN_PINHD-1X1"))
    )
    (comp (ref "JP14")
      (value "GND")
      (footprint "eagle-import:PARTS_AMAN_1X01")
      (libsource (lib "eagle-import") (part "PARTS_AMAN_PINHD-1X1"))
    )
    (comp (ref "JP15")
      (value "LED_T_DV")
      (footprint "eagle-import:PARTS_AMAN_1X01")
      (libsource (lib "eagle-import") (part "PARTS_AMAN_PINHD-1X1"))
    )
    (comp (ref "JP16")
      (value "SW_T_DV")
      (footprint "eagle-import:PARTS_AMAN_1X01")
      (libsource (lib "eagle-import") (part "PARTS_AMAN_PINHD-1X1"))
    )
    (comp (ref "JP17")
      (value "LED_X_DV")
      (footprint "eagle-import:PARTS_AMAN_1X01")
      (libsource (lib "eagle-import") (part "PARTS_AMAN_PINHD-1X1"))
    )
    (comp (ref "JP18")
      (value "SW_X_DV")
      (footprint "eagle-import:PARTS_AMAN_1X01")
      (libsource (lib "eagle-import") (part "PARTS_AMAN_PINHD-1X1"))
    )
    (comp (ref "JP19")
      (value "SW_X_EXT")
      (footprint "eagle-import:PARTS_AMAN_1X01")
      (libsource (lib "eagle-import") (part "PARTS_AMAN_PINHD-1X1"))
    )
    (comp (ref "JP20")
      (value "LED_X_EXT_G")
      (footprint "eagle-import:PARTS_AMAN_1X01")
      (libsource (lib "eagle-import") (part "PARTS_AMAN_PINHD-1X1"))
    )
    (comp (ref "JP21")
      (value "LED_T_RANGE_R")
      (footprint "eagle-import:PARTS_AMAN_1X01")
      (libsource (lib "eagle-import") (part "PARTS_AMAN_PINHD-1X1"))
    )
    (comp (ref "JP22")
      (value "LED_T_RANGE_G")
      (footprint "eagle-import:PARTS_AMAN_1X01")
      (libsource (lib "eagle-import") (part "PARTS_AMAN_PINHD-1X1"))
    )
    (comp (ref "JP30")
      (value "SW_T_RANGE")
      (footprint "eagle-import:PARTS_AMAN_1X01")
      (libsource (lib "eagle-import") (part "PARTS_AMAN_PINHD-1X1"))
    )
    (comp (ref "JP32")
      (value "SW_T_MODE")
      (footprint "eagle-import:PARTS_AMAN_1X01")
      (libsource (lib "eagle-import") (part "PARTS_AMAN_PINHD-1X1"))
    )
    (comp (ref "JP33")
      (value "SW_X_MODE")
      (footprint "eagle-import:PARTS_AMAN_1X01")
      (libsource (lib "eagle-import") (part "PARTS_AMAN_PINHD-1X1"))
    )
    (comp (ref "JP34")
      (value "SW_X_RANGE")
      (footprint "eagle-import:PARTS_AMAN_1X01")
      (libsource (lib "eagle-import") (part "PARTS_AMAN_PINHD-1X1"))
    )
    (comp (ref "JP35")
      (value "LED_T_MODE_R")
      (footprint "eagle-import:PARTS_AMAN_1X01")
      (libsource (lib "eagle-import") (part "PARTS_AMAN_PINHD-1X1"))
    )
    (comp (ref "JP39")
      (value "LED_T_MODE_G")
      (footprint "eagle-import:PARTS_AMAN_1X01")
      (libsource (lib "eagle-import") (part "PARTS_AMAN_PINHD-1X1"))
    )
    (comp (ref "JP40")
      (value "LED_X_MODE_R")
      (footprint "eagle-import:PARTS_AMAN_1X01")
      (libsource (lib "eagle-import") (part "PARTS_AMAN_PINHD-1X1"))
    )
    (comp (ref "JP42")
      (value "LED_X_MODE_G")
      (footprint "eagle-import:PARTS_AMAN_1X01")
      (libsource (lib "eagle-import") (part "PARTS_AMAN_PINHD-1X1"))
    )
    (comp (ref "JP43")
      (value "LED_X_RANGE_R")
      (footprint "eagle-import:PARTS_AMAN_1X01")
      (libsource (lib "eagle-import") (part "PARTS_AMAN_PINHD-1X1"))
    )
    (comp (ref "JP44")
      (value "LED_X_RANGE_G")
      (footprint "eagle-import:PARTS_AMAN_1X01")
      (libsource (lib "eagle-import") (part "PARTS_AMAN_PINHD-1X1"))
    )
    (comp (ref "C1")
      (value "100n")
      (footprint "eagle-import:PARTS_AMAN_RESISTOR_0603")
      (libsource (lib "eagle-import") (part "PARTS_AMAN_CAPACITOR"))
    )
    (comp (ref "C2")
      (value "22u")
      (footprint "eagle-import:PANASONIC_C")
      (libsource (lib "eagle-import") (part "CPOL-USC"))
    )
    (comp (ref "C3")
      (value "22u")
      (footprint "eagle-import:C1206")
      (libsource (lib "eagle-import") (part "C-USC1206"))
    )
    (comp (ref "C5")
      (value "22u")
      (footprint "eagle-import:C1206")
      (libsource (lib "eagle-import") (part "C-USC1206"))
    )
    (comp (ref "C11")
      (value "22u")
      (footprint "eagle-import:PANASONIC_C")
      (libsource (lib "eagle-import") (part "CPOL-USC"))
    )
    (comp (ref "C14")
      (value "22u")
      (footprint "eagle-import:C1206")
      (libsource (lib "eagle-import") (part "C-USC1206"))
    )
    (comp (ref "C22")
      (value "22u")
      (footprint "eagle-import:PANASONIC_C")
      (libsource (lib "eagle-import") (part "CPOL-USC"))
    )
    (comp (ref "C23")
      (value "22u")
      (footprint "eagle-import:PANASONIC_C")
      (libsource (lib "eagle-import") (part "CPOL-USC"))
    )
    (comp (ref "C52")
      (value "470n")
      (footprint "eagle-import:PARTS_AMAN_RESISTOR_0603")
      (libsource (lib "eagle-import") (part "PARTS_AMAN_CAPACITOR"))
    )
    (comp (ref "D1")
      (value "1N5819HW")
      (footprint "eagle-import:SOD123")
      (libsource (lib "eagle-import") (part "DIODE-SOD123"))
    )
    (comp (ref "D2")
      (value "1N5819HW")
      (footprint "eagle-import:SOD123")
      (libsource (lib "eagle-import") (part "DIODE-SOD123"))
    )
    (comp (ref "H3")
      (value "MOUNT-HOLE3.0TINY")
      (footprint "eagle-import:3,0TINY")
      (libsource (lib "eagle-import") (part "MOUNT-HOLE3.0TINY"))
    )
    (comp (ref "H5")
      (value "MOUNT-HOLE3.0TINY")
      (footprint "eagle-import:3,0TINY")
      (libsource (lib "eagle-import") (part "MOUNT-HOLE3.0TINY"))
    )
    (comp (ref "IC1")
      (value "R-78E3.3-0.5")
      (footprint "eagle-import:WE78")
      (libsource (lib "eagle-import") (part "WE173950378"))
    )
    (comp (ref "IC3")
      (value "LD2981ABU33")
      (footprint "eagle-import:SOT89")
      (libsource (lib "eagle-import") (part "LD2981ABU"))
    )
    (comp (ref "IC8")
      (value "LM4040B10")
      (footprint "eagle-import:DBZ_R-PDSO-G3")
      (libsource (lib "eagle-import") (part "LM4041DBZB12"))
    )
    (comp (ref "JP4")
      (value "M05X2SHD")
      (footprint "eagle-import:2X5-SHROUDED")
      (libsource (lib "eagle-import") (part "M05X2SHD"))
    )
    (comp (ref "L1")
      (value "33u")
      (footprint "eagle-import:L2012C")
      (libsource (lib "eagle-import") (part "L-USL2012C"))
    )
    (comp (ref "L2")
      (value "WE-CBF_0603")
      (footprint "eagle-import:0603")
      (libsource (lib "eagle-import") (part "WE-CBF_0603"))
    )
    (comp (ref "L3")
      (value "WE-CBF_0603")
      (footprint "eagle-import:0603")
      (libsource (lib "eagle-import") (part "WE-CBF_0603"))
    )
    (comp (ref "L4")
      (value "WE-CBF_0603")
      (footprint "eagle-import:0603")
      (libsource (lib "eagle-import") (part "WE-CBF_0603"))
    )
    (comp (ref "R68")
      (value "1.0k")
      (footprint "eagle-import:PARTS_AMAN_RESISTOR_0603")
      (libsource (lib "eagle-import") (part "PARTS_AMAN_RESISTOR"))
    )
    (comp (ref "C4")
      (value "20p")
      (footprint "eagle-import:PARTS_AMAN_RESISTOR_0603")
      (libsource (lib "eagle-import") (part "PARTS_AMAN_CAPACITOR"))
    )
    (comp (ref "C6")
      (value "20p")
      (footprint "eagle-import:PARTS_AMAN_RESISTOR_0603")
      (libsource (lib "eagle-import") (part "PARTS_AMAN_CAPACITOR"))
    )
    (comp (ref "C7")
      (value "100n")
      (footprint "eagle-import:PARTS_AMAN_RESISTOR_0603")
      (libsource (lib "eagle-import") (part "PARTS_AMAN_CAPACITOR"))
    )
    (comp (ref "C9")
      (value "100n")
      (footprint "eagle-import:PARTS_AMAN_RESISTOR_0603")
      (libsource (lib "eagle-import") (part "PARTS_AMAN_CAPACITOR"))
    )
    (comp (ref "C10")
      (value "2.2u")
      (footprint "eagle-import:C0805")
      (libsource (lib "eagle-import") (part "C-USC0805"))
    )
    (comp (ref "C12")
      (value "100n")
      (footprint "eagle-import:PARTS_AMAN_RESISTOR_0603")
      (libsource (lib "eagle-import") (part "PARTS_AMAN_CAPACITOR"))
    )
    (comp (ref "C13")
      (value "100n")
      (footprint "eagle-import:PARTS_AMAN_RESISTOR_0603")
      (libsource (lib "eagle-import") (part "PARTS_AMAN_CAPACITOR"))
    )
    (comp (ref "C15")
      (value "2.2u")
      (footprint "eagle-import:C0805")
      (libsource (lib "eagle-import") (part "C-USC0805"))
    )
    (comp (ref "C16")
      (value "100n")
      (footprint "eagle-import:PARTS_AMAN_RESISTOR_0603")
      (libsource (lib "eagle-import") (part "PARTS_AMAN_CAPACITOR"))
    )
    (comp (ref "C19")
      (value "100n")
      (footprint "eagle-import:PARTS_AMAN_RESISTOR_0603")
      (libsource (lib "eagle-import") (part "PARTS_AMAN_CAPACITOR"))
    )
    (comp (ref "C20")
      (value "2.2u")
      (footprint "eagle-import:C0805")
      (libsource (lib "eagle-import") (part "C-USC0805"))
    )
    (comp (ref "C21")
      (value "100n")
      (footprint "eagle-import:PARTS_AMAN_RESISTOR_0603")
      (libsource (lib "eagle-import") (part "PARTS_AMAN_CAPACITOR"))
    )
    (comp (ref "C25")
      (value "470n")
      (footprint "eagle-import:PARTS_AMAN_RESISTOR_0603")
      (libsource (lib "eagle-import") (part "PARTS_AMAN_CAPACITOR"))
    )
    (comp (ref "C26")
      (value "100n")
      (footprint "eagle-import:PARTS_AMAN_RESISTOR_0603")
      (libsource (lib "eagle-import") (part "PARTS_AMAN_CAPACITOR"))
    )
    (comp (ref "C27")
      (value "22u")
      (footprint "eagle-import:PANASONIC_C")
      (libsource (lib "eagle-import") (part "CPOL-USC"))
    )
    (comp (ref "IC2")
      (value "STM32F405RGT6")
      (footprint "eagle-import:TQFP-10X10-64")
      (libsource (lib "eagle-import") (part "STM32F20X"))
    )
    (comp (ref "IC4")
      (value "DAC8164ICPW")
      (footprint "eagle-import:SOP65P640X110-16N")
      (libsource (lib "eagle-import") (part "DAC8564"))
    )
    (comp (ref "JP1")
      (value "M04PTH")
      (footprint "eagle-import:1X04")
      (libsource (lib "eagle-import") (part "M04PTH"))
    )
    (comp (ref "JP2")
      (value "M02PTH")
      (footprint "eagle-import:1X02")
      (libsource (lib "eagle-import") (part "M02PTH"))
    )
    (comp (ref "Q1")
      (value "8MHz")
      (footprint "eagle-import:CTS406")
      (libsource (lib "eagle-import") (part "CRYSTAL"))
    )
    (comp (ref "R2")
      (value "100")
      (footprint "eagle-import:PARTS_AMAN_RESISTOR_0603")
      (libsource (lib "eagle-import") (part "PARTS_AMAN_RESISTOR"))
    )
    (comp (ref "R3")
      (value "100")
      (footprint "eagle-import:PARTS_AMAN_RESISTOR_0603")
      (libsource (lib "eagle-import") (part "PARTS_AMAN_RESISTOR"))
    )
    (comp (ref "R6")
      (value "10k")
      (footprint "eagle-import:PARTS_AMAN_RESISTOR_0603")
      (libsource (lib "eagle-import") (part "PARTS_AMAN_RESISTOR"))
    )
    (comp (ref "R7")
      (value "100")
      (footprint "eagle-import:PARTS_AMAN_RESISTOR_0603")
      (libsource (lib "eagle-import") (part "PARTS_AMAN_RESISTOR"))
    )
    (comp (ref "R8")
      (value "100")
      (footprint "eagle-import:PARTS_AMAN_RESISTOR_0603")
      (libsource (lib "eagle-import") (part "PARTS_AMAN_RESISTOR"))
    )
  )
  (nets
    (net (code "1") (name "+3V3") (class "Default")
      (node (ref "C1") (pin "1") (pinfunction "1_1") (pintype "passive"))
      (node (ref "C12") (pin "1") (pinfunction "1_1") (pintype "passive"))
      (node (ref "C13") (pin "1") (pinfunction "1_1") (pintype "passive"))
      (node (ref "C16") (pin "1") (pinfunction "1_1") (pintype "passive"))
      (node (ref "C19") (pin "1") (pinfunction "1_1") (pintype "passive"))
      (node (ref "C2") (pin "+") (pinfunction "+_+") (pintype "passive"))
      (node (ref "C21") (pin "1") (pinfunction "1_1") (pintype "passive"))
      (node (ref "IC1") (pin "3") (pinfunction "VO_3") (pintype "passive"))
      (node (ref "IC2") (pin "1") (pinfunction "VBAT_1") (pintype "power_in"))
      (node (ref "IC2") (pin "19") (pinfunction "VDD_4_19") (pintype "power_in"))
      (node (ref "IC2") (pin "32") (pinfunction "VDD_1_32") (pintype "power_in"))
      (node (ref "IC2") (pin "48") (pinfunction "VDD_2_48") (pintype "power_in"))
      (node (ref "IC2") (pin "64") (pinfunction "VDD_3_64") (pintype "power_in"))
      (node (ref "IC4") (pin "12") (pinfunction "DVDD_12") (pintype "power_in"))
      (node (ref "R22") (pin "2") (pinfunction "2_2") (pintype "passive"))
      (node (ref "R23") (pin "2") (pinfunction "2_2") (pintype "passive"))
      (node (ref "R6") (pin "2") (pinfunction "2_2") (pintype "passive"))
    )
    (net (code "2") (name "+3V3_A") (class "Default")
      (node (ref "C10") (pin "1") (pinfunction "1_1") (pintype "passive"))
      (node (ref "C23") (pin "+") (pinfunction "+_+") (pintype "passive"))
      (node (ref "C26") (pin "1") (pinfunction "1_1") (pintype "passive"))
      (node (ref "C27") (pin "+") (pinfunction "+_+") (pintype "passive"))
      (node (ref "C46") (pin "1") (pinfunction "1_1") (pintype "passive"))
      (node (ref "C47") (pin "1") (pinfunction "1_1") (pintype "passive"))
      (node (ref "C9") (pin "1") (pinfunction "1_1") (pintype "passive"))
      (node (ref "IC2") (pin "13") (pinfunction "VDDA_13") (pintype "power_in"))
      (node (ref "IC3") (pin "1") (pinfunction "VO_1") (pintype "passive"))
      (node (ref "IC4") (pin "4") (pinfunction "AVDD_4") (pintype "power_in"))
      (node (ref "IC5") (pin "4") (pinfunction "V+_4") (pintype "power_in"))
      (node (ref "IC6") (pin "4") (pinfunction "V+_4") (pintype "power_in"))
      (node (ref "JP13") (pin "1") (pinfunction "1_1") (pintype "passive"))
    )
    (net (code "3") (name "ADC_DV_CV") (class "Default")
      (node (ref "C33") (pin "2") (pinfunction "2_2") (pintype "passive"))
      (node (ref "IC2") (pin "21") (pinfunction "PA5/SPI1_SCK/ADC5/DAC2_21") (pintype "bidirectional"))
      (node (ref "IC6") (pin "8") (pinfunction "OUT_8") (pintype "output"))
      (node (ref "R42") (pin "1") (pinfunction "1_1") (pintype "passive"))
    )
    (net (code "4") (name "ADC_DV_POT") (class "Default")
      (node (ref "IC2") (pin "11") (pinfunction "PC3/SPI2_MOSI/I2S2_SD/ADC13_11") (pintype "bidirectional"))
      (node (ref "JP11") (pin "1") (pinfunction "1_1") (pintype "passive"))
    )
    (net (code "5") (name "ADC_LENGTH_POT") (class "Default")
      (node (ref "IC2") (pin "27") (pinfunction "PB1/ADC9/TIM3_CH4_27") (pintype "bidirectional"))
      (node (ref "JP12") (pin "1") (pinfunction "1_1") (pintype "passive"))
    )
    (net (code "6") (name "ADC_T_BIAS_CV") (class "Default")
      (node (ref "C40") (pin "2") (pinfunction "2_2") (pintype "passive"))
      (node (ref "IC2") (pin "15") (pinfunction "PA1/USART2_RTS/UART4_RX/ADC1/TIM2_CH2_15") (pintype "bidirectional"))
      (node (ref "IC5") (pin "1") (pinfunction "OUT_1") (pintype "output"))
      (node (ref "R57") (pin "1") (pinfunction "1_1") (pintype "passive"))
    )
    (net (code "7") (name "ADC_T_BIAS_POT") (class "Default")
      (node (ref "IC2") (pin "16") (pinfunction "PA2/USART2_TX/ADC2/TIM2_CH3_16") (pintype "bidirectional"))
      (node (ref "JP5") (pin "1") (pinfunction "1_1") (pintype "passive"))
    )
    (net (code "8") (name "ADC_T_JITTER_CV") (class "Default")
      (node (ref "C42") (pin "2") (pinfunction "2_2") (pintype "passive"))
      (node (ref "IC2") (pin "20") (pinfunction "PA4/SPI1_NSS/SPI3_NSS/USART2_CK/I2S3_WS/ADC4/DAC1_20") (pintype "bidirectional"))
      (node (ref "IC6") (pin "7") (pinfunction "OUT_7") (pintype "output"))
      (node (ref "R59") (pin "1") (pinfunction "1_1") (pintype "passive"))
    )
    (net (code "9") (name "ADC_T_JITTER_POT") (class "Default")
      (node (ref "IC2") (pin "25") (pinfunction "PC5/ADC15_25") (pintype "bidirectional"))
      (node (ref "JP7") (pin "1") (pinfunction "1_1") (pintype "passive"))
    )
    (net (code "10") (name "ADC_T_RATE_CV") (class "Default")
      (node (ref "C41") (pin "2") (pinfunction "2_2") (pintype "passive"))
      (node (ref "IC2") (pin "17") (pinfunction "PA3/USART2_RX/ADC3/TIM2_CH4_17") (pintype "bidirectional"))
      (node (ref "IC6") (pin "1") (pinfunction "OUT_1") (pintype "output"))
      (node (ref "R58") (pin "1") (pinfunction "1_1") (pintype "passive"))
    )
    (net (code "11") (name "ADC_T_RATE_POT") (class "Default")
      (node (ref "IC2") (pin "10") (pinfunction "PC2/SPI2_MISO/ADC12_10") (pintype "bidirectional"))
      (node (ref "JP6") (pin "1") (pinfunction "1_1") (pintype "passive"))
    )
    (net (code "12") (name "ADC_X_BIAS_CV") (class "Default")
      (node (ref "C30") (pin "2") (pinfunction "2_2") (pintype "passive"))
      (node (ref "IC2") (pin "24") (pinfunction "PC4/ADC14_24") (pintype "bidirectional"))
      (node (ref "IC5") (pin "14") (pinfunction "OUT_14") (pintype "output"))
      (node (ref "R39") (pin "1") (pinfunction "1_1") (pintype "passive"))
    )
    (net (code "13") (name "ADC_X_BIAS_POT") (class "Default")
      (node (ref "IC2") (pin "9") (pinfunction "PC1/ADC11_9") (pintype "bidirectional"))
      (node (ref "JP10") (pin "1") (pinfunction "1_1") (pintype "passive"))
    )
    (net (code "14") (name "ADC_X_SPREAD_CV") (class "Default")
      (node (ref "C31") (pin "2") (pinfunction "2_2") (pintype "passive"))
      (node (ref "IC2") (pin "14") (pinfunction "PA0-WKUP/USART2_CTS/UART4_TX/ADC0/TIM2_CH1_ETR_14") (pintype "bidirectional"))
      (node (ref "IC2") (pin "23") (pinfunction "PA7/SPI1_MOSI/ADC7/TIM3_CH2_23") (pintype "bidirectional"))
      (node (ref "IC5") (pin "8") (pinfunction "OUT_8") (pintype "output"))
      (node (ref "R40") (pin "1") (pinfunction "1_1") (pintype "passive"))
    )
    (net (code "15") (name "ADC_X_SPREAD_POT") (class "Default")
      (node (ref "IC2") (pin "8") (pinfunction "PC0/ADC10_8") (pintype "bidirectional"))
      (node (ref "JP9") (pin "1") (pinfunction "1_1") (pintype "passive"))
    )
    (net (code "16") (name "ADC_X_STEPS_CV") (class "Default")
      (node (ref "C32") (pin "2") (pinfunction "2_2") (pintype "passive"))
      (node (ref "IC2") (pin "22") (pinfunction "PA6/SPI1_MISO/ADC6/TIM3_CH1_22") (pintype "bidirectional"))
      (node (ref "IC6") (pin "14") (pinfunction "OUT_14") (pintype "output"))
      (node (ref "R41") (pin "1") (pinfunction "1_1") (pintype "passive"))
    )
    (net (code "17") (name "ADC_X_STEPS_POT") (class "Default")
      (node (ref "IC2") (pin "26") (pinfunction "PB0/ADC8/TIM3_CH3_26") (pintype "bidirectional"))
      (node (ref "JP8") (pin "1") (pinfunction "1_1") (pintype "passive"))
    )
    (net (code "18") (name "AREF_-10") (class "Default")
      (node (ref "C52") (pin "1") (pinfunction "1_1") (pintype "passive"))
      (node (ref "IC8") (pin "2") (pinfunction "A_2") (pintype "passive"))
      (node (ref "R28") (pin "2") (pinfunction "2_2") (pintype "passive"))
      (node (ref "R29") (pin "2") (pinfunction "2_2") (pintype "passive"))
      (node (ref "R30") (pin "2") (pinfunction "2_2") (pintype "passive"))
      (node (ref "R31") (pin "2") (pinfunction "2_2") (pintype "passive"))
      (node (ref "R68") (pin "2") (pinfunction "2_2") (pintype "passive"))
      (node (ref "R70") (pin "2") (pinfunction "2_2") (pintype "passive"))
      (node (ref "R71") (pin "2") (pinfunction "2_2") (pintype "passive"))
      (node (ref "R72") (pin "2") (pinfunction "2_2") (pintype "passive"))
    )
    (net (code "19") (name "DAC_MOSI") (class "Default")
      (node (ref "IC2") (pin "53") (pinfunction "PC12/UART5_TX/I2S3_SD/USART3_CK_53") (pintype "bidirectional"))
      (node (ref "IC4") (pin "11") (pinfunction "IN_11") (pintype "input"))
    )
    (net (code "20") (name "DAC_SCK") (class "Default")
      (node (ref "IC2") (pin "51") (pinfunction "PC10/SPI3_SCK/I2S3_SCK/UART4_TX_51") (pintype "bidirectional"))
      (node (ref "IC4") (pin "10") (pinfunction "SCK_10") (pintype "input"))
    )
    (net (code "21") (name "DAC_SS") (class "Default")
      (node (ref "IC2") (pin "50") (pinfunction "PA15/JTDI/SPI3_NSS/I2S3_WS_50") (pintype "bidirectional"))
      (node (ref "IC4") (pin "9") (pinfunction "SYNC_9") (pintype "input"))
    )
    (net (code "22") (name "DAC_X_1") (class "Default")
      (node (ref "IC4") (pin "2") (pinfunction "OUTB_2") (pintype "output"))
      (node (ref "R47") (pin "2") (pinfunction "2_2") (pintype "passive"))
    )
    (net (code "23") (name "DAC_X_2") (class "Default")
      (node (ref "IC4") (pin "7") (pinfunction "OUTC_7") (pintype "output"))
      (node (ref "R48") (pin "2") (pinfunction "2_2") (pintype "passive"))
    )
    (net (code "24") (name "DAC_X_3") (class "Default")
      (node (ref "IC4") (pin "8") (pinfunction "OUTD_8") (pintype "output"))
      (node (ref "R53") (pin "2") (pinfunction "2_2") (pintype "passive"))
    )
    (net (code "25") (name "DAC_Y") (class "Default")
      (node (ref "IC4") (pin "1") (pinfunction "OUTA_1") (pintype "output"))
      (node (ref "R54") (pin "2") (pinfunction "2_2") (pintype "passive"))
    )
    (net (code "26") (name "DEPRECATED") (class "Default")
      (node (ref "IC5") (pin "6") (pinfunction "-IN_6") (pintype "input"))
      (node (ref "IC5") (pin "7") (pinfunction "OUT_7") (pintype "output"))
    )
    (net (code "27") (name "GATE_T_1") (class "Default")
      (node (ref "IC2") (pin "52") (pinfunction "PC11/UART4_RX/SPI3_MISO/USART3_RX_52") (pintype "bidirectional"))
      (node (ref "JP54") (pin "1") (pinfunction "1_1") (pintype "passive"))
      (node (ref "R56") (pin "2") (pinfunction "2_2") (pintype "passive"))
    )
    (net (code "28") (name "GATE_T_2") (class "Default")
      (node (ref "IC2") (pin "44") (pinfunction "PA11/USART1_CTS/CANRX/USBDM/TIM1_CH4_44") (pintype "bidirectional"))
      (node (ref "JP56") (pin "1") (pinfunction "1_1") (pintype "passive"))
      (node (ref "R55") (pin "2") (pinfunction "2_2") (pintype "passive"))
    )
    (net (code "29") (name "GATE_T_3") (class "Default")
      (node (ref "IC2") (pin "45") (pinfunction "PA12/USART1_RTS/CANTX/USBDP/TIM1_ETR_45") (pintype "bidirectional"))
      (node (ref "JP57") (pin "1") (pinfunction "1_1") (pintype "passive"))
      (node (ref "R67") (pin "2") (pinfunction "2_2") (pintype "passive"))
    )
    (net (code "30") (name "GND") (class "Default")
      (node (ref "C1") (pin "2") (pinfunction "2_2") (pintype "passive"))
      (node (ref "C10") (pin "2") (pinfunction "2_2") (pintype "passive"))
      (node (ref "C11") (pin "-") (pinfunction "-_-") (pintype "passive"))
      (node (ref "C12") (pin "2") (pinfunction "2_2") (pintype "passive"))
      (node (ref "C13") (pin "2") (pinfunction "2_2") (pintype "passive"))
      (node (ref "C14") (pin "2") (pinfunction "2_2") (pintype "passive"))
      (node (ref "C15") (pin "2") (pinfunction "2_2") (pintype "passive"))
      (node (ref "C16") (pin "2") (pinfunction "2_2") (pintype "passive"))
      (node (ref "C19") (pin "2") (pinfunction "2_2") (pintype "passive"))
      (node (ref "C2") (pin "-") (pinfunction "-_-") (pintype "passive"))
      (node (ref "C20") (pin "2") (pinfunction "2_2") (pintype "passive"))
      (node (ref "C21") (pin "2") (pinfunction "2_2") (pintype "passive"))
      (node (ref "C22") (pin "+") (pinfunction "+_+") (pintype "passive"))
      (node (ref "C23") (pin "-") (pinfunction "-_-") (pintype "passive"))
      (node (ref "C25") (pin "2") (pinfunction "2_2") (pintype "passive"))
      (node (ref "C26") (pin "2") (pinfunction "2_2") (pintype "passive"))
      (node (ref "C27") (pin "-") (pinfunction "-_-") (pintype "passive"))
      (node (ref "C3") (pin "2") (pinfunction "2_2") (pintype "passive"))
      (node (ref "C37") (pin "1") (pinfunction "1_1") (pintype "passive"))
      (node (ref "C39") (pin "2") (pinfunction "2_2") (pintype "passive"))
      (node (ref "C4") (pin "1") (pinfunction "1_1") (pintype "passive"))
      (node (ref "C46") (pin "2") (pinfunction "2_2") (pintype "passive"))
      (node (ref "C47") (pin "2") (pinfunction "2_2") (pintype "passive"))
      (node (ref "C5") (pin "2") (pinfunction "2_2") (pintype "passive"))
      (node (ref "C50") (pin "2") (pinfunction "2_2") (pintype "passive"))
      (node (ref "C51") (pin "2") (pinfunction "2_2") (pintype "passive"))
      (node (ref "C52") (pin "2") (pinfunction "2_2") (pintype "passive"))
      (node (ref "C6") (pin "1") (pinfunction "1_1") (pintype "passive"))
      (node (ref "C7") (pin "2") (pinfunction "2_2") (pintype "passive"))
      (node (ref "C9") (pin "2") (pinfunction "2_2") (pintype "passive"))
      (node (ref "D4") (pin "2") (pinfunction "A_2") (pintype "bidirectional"))
      (node (ref "D5") (pin "2") (pinfunction "A_2") (pintype "bidirectional"))
      (node (ref "IC1") (pin "2") (pinfunction "GND_2") (pintype "passive"))
      (node (ref "IC2") (pin "12") (pinfunction "VSSA_12") (pintype "power_in"))
      (node (ref "IC2") (pin "18") (pinfunction "VSS_4_18") (pintype "power_in"))
      (node (ref "IC2") (pin "28") (pinfunction "PB2/BOOT1_28") (pintype "bidirectional"))
      (node (ref "IC2") (pin "60") (pinfunction "BOOT0_60") (pintype "bidirectional"))
      (node (ref "IC2") (pin "63") (pinfunction "VSS_3_63") (pintype "power_in"))
      (node (ref "IC3") (pin "2") (pinfunction "GND_2") (pintype "passive"))
      (node (ref "IC4") (pin "13") (pinfunction "A0_13") (pintype "input"))
      (node (ref "IC4") (pin "14") (pinfunction "A1_14") (pintype "input"))
      (node (ref "IC4") (pin "15") (pinfunction "ENABLE_15") (pintype "input"))
      (node (ref "IC4") (pin "16") (pinfunction "LDAC_16") (pintype "input"))
      (node (ref "IC4") (pin "5") (pinfunction "VREFL_5") (pintype "bidirectional"))
      (node (ref "IC4") (pin "6") (pinfunction "GND_6") (pintype "power_in"))
      (node (ref "IC5") (pin "10") (pinfunction "+IN_10") (pintype "input"))
      (node (ref "IC5") (pin "11") (pinfunction "V-_11") (pintype "power_in"))
      (node (ref "IC5") (pin "12") (pinfunction "+IN_12") (pintype "input"))
      (node (ref "IC5") (pin "3") (pinfunction "+IN_3") (pintype "input"))
      (node (ref "IC5") (pin "5") (pinfunction "+IN_5") (pintype "input"))
      (node (ref "IC6") (pin "10") (pinfunction "+IN_10") (pintype "input"))
      (node (ref "IC6") (pin "11") (pinfunction "V-_11") (pintype "power_in"))
      (node (ref "IC6") (pin "12") (pinfunction "+IN_12") (pintype "input"))
      (node (ref "IC6") (pin "3") (pinfunction "+IN_3") (pintype "input"))
      (node (ref "IC6") (pin "5") (pinfunction "+IN_5") (pintype "input"))
      (node (ref "IC8") (pin "1") (pinfunction "C_1") (pintype "passive"))
      (node (ref "IC9") (pin "11") (pinfunction "V-_11") (pintype "power_in"))
      (node (ref "IC9") (pin "5") (pinfunction "+IN_5") (pintype "input"))
      (node (ref "JP1") (pin "2") (pinfunction "2_2") (pintype "passive"))
      (node (ref "JP14") (pin "1") (pinfunction "1_1") (pintype "passive"))
      (node (ref "JP3") (pin "1") (pinfunction "1_1") (pintype "passive"))
      (node (ref "JP4") (pin "3") (pinfunction "3_3") (pintype "passive"))
      (node (ref "JP4") (pin "4") (pinfunction "4_4") (pintype "passive"))
      (node (ref "JP4") (pin "5") (pinfunction "5_5") (pintype "passive"))
      (node (ref "JP4") (pin "6") (pinfunction "6_6") (pintype "passive"))
      (node (ref "JP4") (pin "7") (pinfunction "7_7") (pintype "passive"))
      (node (ref "JP4") (pin "8") (pinfunction "8_8") (pintype "passive"))
      (node (ref "Q1") (pin "2") (pinfunction "LID1_2") (pintype "power_in"))
      (node (ref "Q1") (pin "4") (pinfunction "LID2_4") (pintype "power_in"))
      (node (ref "Q2") (pin "E") (pinfunction "E_E") (pintype "passive"))
      (node (ref "Q3") (pin "E") (pinfunction "E_E") (pintype "passive"))
      (node (ref "R24") (pin "1") (pinfunction "1_1") (pintype "passive"))
      (node (ref "R25") (pin "1") (pinfunction "1_1") (pintype "passive"))
      (node (ref "R49") (pin "2") (pinfunction "2_2") (pintype "passive"))
      (node (ref "R50") (pin "2") (pinfunction "2_2") (pintype "passive"))
      (node (ref "R73") (pin "1") (pinfunction "1_1") (pintype "passive"))
      (node (ref "R75") (pin "2") (pinfunction "2_2") (pintype "passive"))
    )
    (net (code "31") (name "LED_T_DV") (class "Default")
      (node (ref "IC2") (pin "29") (pinfunction "PB10/SPI2_SCK/I2S_SCK/I2C2_SCL/USART3_TX_29") (pintype "bidirectional"))
      (node (ref "JP15") (pin "1") (pinfunction "1_1") (pintype "passive"))
    )
    (net (code "32") (name "LED_T_MODE_G") (class "Default")
      (node (ref "IC2") (pin "33") (pinfunction "PB12/SPI2_NSS/I2S2_WS/I2C2_SMBA/USART3_CK/TIM1_BKIN_33") (pintype "bidirectional"))
      (node (ref "JP39") (pin "1") (pinfunction "1_1") (pintype "passive"))
    )
    (net (code "33") (name "LED_T_MODE_R") (class "Default")
      (node (ref "IC2") (pin "34") (pinfunction "PB13/SPI2_SCK/I2S2_SCK/USART3_CTS/TIM1_CH1N_34") (pintype "bidirectional"))
      (node (ref "JP35") (pin "1") (pinfunction "1_1") (pintype "passive"))
    )
    (net (code "34") (name "LED_T_RANGE_G") (class "Default")
      (node (ref "IC2") (pin "37") (pinfunction "PC6/I2S2_MCK_37") (pintype "bidirectional"))
      (node (ref "JP22") (pin "1") (pinfunction "1_1") (pintype "passive"))
    )
    (net (code "35") (name "LED_T_RANGE_R") (class "Default")
      (node (ref "IC2") (pin "38") (pinfunction "PC7/I2S3_MCK_38") (pintype "bidirectional"))
      (node (ref "JP21") (pin "1") (pinfunction "1_1") (pintype "passive"))
    )
    (net (code "36") (name "LED_X_DV") (class "Default")
      (node (ref "IC2") (pin "62") (pinfunction "PB9/SPI2_NSS/I2S2_WS/I2C1_SDA/TIM4_CH4_62") (pintype "bidirectional"))
      (node (ref "JP17") (pin "1") (pinfunction "1_1") (pintype "passive"))
    )
    (net (code "37") (name "LED_X_EXT_G") (class "Default")
      (node (ref "IC2") (pin "55") (pinfunction "PB3/JTDO/SPI3_SCK/I2S3_SCK_55") (pintype "bidirectional"))
      (node (ref "JP20") (pin "1") (pinfunction "1_1") (pintype "passive"))
    )
    (net (code "38") (name "LED_X_MODE_G") (class "Default")
      (node (ref "IC2") (pin "59") (pinfunction "PB7/I2C1_SDA/TIM4_CH2/USART1_RX_59") (pintype "bidirectional"))
      (node (ref "JP42") (pin "1") (pinfunction "1_1") (pintype "passive"))
    )
    (net (code "39") (name "LED_X_MODE_R") (class "Default")
      (node (ref "IC2") (pin "61") (pinfunction "PB8/TIM4_CH3/I2C1_SCL_61") (pintype "bidirectional"))
      (node (ref "JP40") (pin "1") (pinfunction "1_1") (pintype "passive"))
    )
    (net (code "40") (name "LED_X_RANGE_G") (class "Default")
      (node (ref "IC2") (pin "57") (pinfunction "PB5/I2C1_SMBA/SPI1_MOSI/SPI3_MOSI/I2S3_SD_57") (pintype "bidirectional"))
      (node (ref "JP44") (pin "1") (pinfunction "1_1") (pintype "passive"))
    )
    (net (code "41") (name "LED_X_RANGE_R") (class "Default")
      (node (ref "IC2") (pin "56") (pinfunction "PB4/NJTRST/SPI3_MISO/SPI1_MISO_56") (pintype "bidirectional"))
      (node (ref "JP43") (pin "1") (pinfunction "1_1") (pintype "passive"))
    )
    (net (code "42") (name "NORMALIZATION_PROBE") (class "Default")
      (node (ref "IC2") (pin "39") (pinfunction "PC8_39") (pintype "bidirectional"))
      (node (ref "JP37") (pin "1") (pinfunction "1_1") (pintype "passive"))
    )
    (net (code "43") (name "Net-(C5-Pad1)") (class "Default")
      (node (ref "C5") (pin "1") (pinfunction "1_1") (pintype "passive"))
      (node (ref "D1") (pin "C") (pinfunction "C_C") (pintype "passive"))
      (node (ref "L1") (pin "1") (pinfunction "1_1") (pintype "passive"))
      (node (ref "L2") (pin "2") (pinfunction "2_2") (pintype "passive"))
      (node (ref "L3") (pin "2") (pinfunction "2_2") (pintype "passive"))
    )
    (net (code "44") (name "Net-(C6-Pad2)") (class "Default")
      (node (ref "C6") (pin "2") (pinfunction "2_2") (pintype "passive"))
      (node (ref "Q1") (pin "1") (pinfunction "1_1") (pintype "passive"))
      (node (ref "R7") (pin "2") (pinfunction "2_2") (pintype "passive"))
    )
    (net (code "45") (name "Net-(D1-PadA)") (class "Default")
      (node (ref "D1") (pin "A") (pinfunction "A_A") (pintype "passive"))
      (node (ref "JP4") (pin "10") (pinfunction "10_10") (pintype "passive"))
      (node (ref "JP4") (pin "9") (pinfunction "9_9") (pintype "passive"))
    )
    (net (code "46") (name "Net-(D2-PadA)") (class "Default")
      (node (ref "D2") (pin "A") (pinfunction "A_A") (pintype "passive"))
      (node (ref "L4") (pin "2") (pinfunction "2_2") (pintype "passive"))
    )
    (net (code "47") (name "Net-(D2-PadC)") (class "Default")
      (node (ref "D2") (pin "C") (pinfunction "C_C") (pintype "passive"))
      (node (ref "JP4") (pin "1") (pinfunction "1_1") (pintype "passive"))
      (node (ref "JP4") (pin "2") (pinfunction "2_2") (pintype "passive"))
    )
    (net (code "48") (name "Net-(D4-K)") (class "Default")
      (node (ref "D4") (pin "1") (pinfunction "K_1") (pintype "bidirectional"))
      (node (ref "JP23") (pin "1") (pinfunction "1_1") (pintype "passive"))
      (node (ref "Q2") (pin "B") (pinfunction "B_B") (pintype "passive"))
      (node (ref "R24") (pin "2") (pinfunction "2_2") (pintype "passive"))
    )
    (net (code "49") (name "Net-(D5-K)") (class "Default")
      (node (ref "D5") (pin "1") (pinfunction "K_1") (pintype "bidirectional"))
      (node (ref "JP24") (pin "1") (pinfunction "1_1") (pintype "passive"))
      (node (ref "Q3") (pin "B") (pinfunction "B_B") (pintype "passive"))
      (node (ref "R25") (pin "2") (pinfunction "2_2") (pintype "passive"))
    )
    (net (code "50") (name "Net-(IC1-VI)") (class "Default")
      (node (ref "C3") (pin "1") (pinfunction "1_1") (pintype "passive"))
      (node (ref "IC1") (pin "1") (pinfunction "VI_1") (pintype "input"))
      (node (ref "L1") (pin "2") (pinfunction "2_2") (pintype "passive"))
    )
    (net (code "51") (name "Net-(IC2-PD0{slash}OSC_IN)") (class "Default")
      (node (ref "IC2") (pin "5") (pinfunction "PD0/OSC_IN_5") (pintype "bidirectional"))
      (node (ref "R8") (pin "1") (pinfunction "1_1") (pintype "passive"))
    )
    (net (code "52") (name "Net-(IC2-PD1{slash}OSC_OUT)") (class "Default")
      (node (ref "IC2") (pin "6") (pinfunction "PD1/OSC_OUT_6") (pintype "bidirectional"))
      (node (ref "R7") (pin "1") (pinfunction "1_1") (pintype "passive"))
    )
    (net (code "53") (name "Net-(IC2-VCAP_1)") (class "Default")
      (node (ref "C15") (pin "1") (pinfunction "1_1") (pintype "passive"))
      (node (ref "IC2") (pin "31") (pinfunction "VCAP_1_31") (pintype "power_in"))
    )
    (net (code "54") (name "Net-(IC2-VCAP_2)") (class "Default")
      (node (ref "C20") (pin "1") (pinfunction "1_1") (pintype "passive"))
      (node (ref "IC2") (pin "47") (pinfunction "VCAP_2_47") (pintype "power_in"))
    )
    (net (code "55") (name "Net-(IC3-VI)") (class "Default")
      (node (ref "C14") (pin "1") (pinfunction "1_1") (pintype "passive"))
      (node (ref "IC3") (pin "3") (pinfunction "VI_3") (pintype "input"))
      (node (ref "L3") (pin "1") (pinfunction "1_1") (pintype "passive"))
    )
    (net (code "56") (name "Net-(IC5A--IN)") (class "Default")
      (node (ref "C40") (pin "1") (pinfunction "1_1") (pintype "passive"))
      (node (ref "IC5") (pin "2") (pinfunction "-IN_2") (pintype "input"))
      (node (ref "R57") (pin "2") (pinfunction "2_2") (pintype "passive"))
      (node (ref "R64") (pin "1") (pinfunction "1_1") (pintype "passive"))
      (node (ref "R70") (pin "1") (pinfunction "1_1") (pintype "passive"))
    )
    (net (code "57") (name "Net-(IC5C--IN)") (class "Default")
      (node (ref "C31") (pin "1") (pinfunction "1_1") (pintype "passive"))
      (node (ref "IC5") (pin "9") (pinfunction "-IN_9") (pintype "input"))
      (node (ref "R28") (pin "1") (pinfunction "1_1") (pintype "passive"))
      (node (ref "R34") (pin "1") (pinfunction "1_1") (pintype "passive"))
      (node (ref "R40") (pin "2") (pinfunction "2_2") (pintype "passive"))
    )
    (net (code "58") (name "Net-(IC5D--IN)") (class "Default")
      (node (ref "C30") (pin "1") (pinfunction "1_1") (pintype "passive"))
      (node (ref "IC5") (pin "13") (pinfunction "-IN_13") (pintype "input"))
      (node (ref "R30") (pin "1") (pinfunction "1_1") (pintype "passive"))
      (node (ref "R33") (pin "1") (pinfunction "1_1") (pintype "passive"))
      (node (ref "R39") (pin "2") (pinfunction "2_2") (pintype "passive"))
    )
    (net (code "59") (name "Net-(IC6A--IN)") (class "Default")
      (node (ref "C41") (pin "1") (pinfunction "1_1") (pintype "passive"))
      (node (ref "IC6") (pin "2") (pinfunction "-IN_2") (pintype "input"))
      (node (ref "R58") (pin "2") (pinfunction "2_2") (pintype "passive"))
      (node (ref "R65") (pin "1") (pinfunction "1_1") (pintype "passive"))
      (node (ref "R71") (pin "1") (pinfunction "1_1") (pintype "passive"))
    )
    (net (code "60") (name "Net-(IC6B--IN)") (class "Default")
      (node (ref "C42") (pin "1") (pinfunction "1_1") (pintype "passive"))
      (node (ref "IC6") (pin "6") (pinfunction "-IN_6") (pintype "input"))
      (node (ref "R59") (pin "2") (pinfunction "2_2") (pintype "passive"))
      (node (ref "R66") (pin "1") (pinfunction "1_1") (pintype "passive"))
      (node (ref "R72") (pin "1") (pinfunction "1_1") (pintype "passive"))
    )
    (net (code "61") (name "Net-(IC6C--IN)") (class "Default")
      (node (ref "C33") (pin "1") (pinfunction "1_1") (pintype "passive"))
      (node (ref "IC6") (pin "9") (pinfunction "-IN_9") (pintype "input"))
      (node (ref "R31") (pin "1") (pinfunction "1_1") (pintype "passive"))
      (node (ref "R32") (pin "1") (pinfunction "1_1") (pintype "passive"))
      (node (ref "R42") (pin "2") (pinfunction "2_2") (pintype "passive"))
    )
    (net (code "62") (name "Net-(IC6D--IN)") (class "Default")
      (node (ref "C32") (pin "1") (pinfunction "1_1") (pintype "passive"))
      (node (ref "IC6") (pin "13") (pinfunction "-IN_13") (pintype "input"))
      (node (ref "R29") (pin "1") (pinfunction "1_1") (pintype "passive"))
      (node (ref "R35") (pin "1") (pinfunction "1_1") (pintype "passive"))
      (node (ref "R41") (pin "2") (pinfunction "2_2") (pintype "passive"))
    )
    (net (code "63") (name "Net-(IC7A--IN)") (class "Default")
      (node (ref "C34") (pin "1") (pinfunction "1_1") (pintype "passive"))
      (node (ref "IC7") (pin "2") (pinfunction "-IN_2") (pintype "input"))
      (node (ref "R43") (pin "2") (pinfunction "2_2") (pintype "passive"))
      (node (ref "R47") (pin "1") (pinfunction "1_1") (pintype "passive"))
    )
    (net (code "64") (name "Net-(IC7A-OUT)") (class "Default")
      (node (ref "C34") (pin "2") (pinfunction "2_2") (pintype "passive"))
      (node (ref "IC7") (pin "1") (pinfunction "OUT_1") (pintype "output"))
      (node (ref "JP47") (pin "1") (pinfunction "1_1") (pintype "passive"))
      (node (ref "R45") (pin "2") (pinfunction "2_2") (pintype "passive"))
    )
    (net (code "65") (name "Net-(IC7B--IN)") (class "Default")
      (node (ref "C43") (pin "1") (pinfunction "1_1") (pintype "passive"))
      (node (ref "IC7") (pin "6") (pinfunction "-IN_6") (pintype "input"))
      (node (ref "R54") (pin "1") (pinfunction "1_1") (pintype "passive"))
      (node (ref "R60") (pin "2") (pinfunction "2_2") (pintype "passive"))
    )
    (net (code "66") (name "Net-(IC7B-OUT)") (class "Default")
      (node (ref "C43") (pin "2") (pinfunction "2_2") (pintype "passive"))
      (node (ref "IC7") (pin "7") (pinfunction "OUT_7") (pintype "output"))
      (node (ref "JP41") (pin "1") (pinfunction "1_1") (pintype "passive"))
      (node (ref "R62") (pin "2") (pinfunction "2_2") (pintype "passive"))
    )
    (net (code "67") (name "Net-(IC7C--IN)") (class "Default")
      (node (ref "C44") (pin "1") (pinfunction "1_1") (pintype "passive"))
      (node (ref "IC7") (pin "9") (pinfunction "-IN_9") (pintype "input"))
      (node (ref "R53") (pin "1") (pinfunction "1_1") (pintype "passive"))
      (node (ref "R61") (pin "2") (pinfunction "2_2") (pintype "passive"))
    )
    (net (code "68") (name "Net-(IC7C-OUT)") (class "Default")
      (node (ref "C44") (pin "2") (pinfunction "2_2") (pintype "passive"))
      (node (ref "IC7") (pin "8") (pinfunction "OUT_8") (pintype "output"))
      (node (ref "JP53") (pin "1") (pinfunction "1_1") (pintype "passive"))
      (node (ref "R63") (pin "2") (pinfunction "2_2") (pintype "passive"))
    )
    (net (code "69") (name "Net-(IC7D--IN)") (class "Default")
      (node (ref "C35") (pin "1") (pinfunction "1_1") (pintype "passive"))
      (node (ref "IC7") (pin "13") (pinfunction "-IN_13") (pintype "input"))
      (node (ref "R44") (pin "2") (pinfunction "2_2") (pintype "passive"))
      (node (ref "R48") (pin "1") (pinfunction "1_1") (pintype "passive"))
    )
    (net (code "70") (name "Net-(IC7D-OUT)") (class "Default")
      (node (ref "C35") (pin "2") (pinfunction "2_2") (pintype "passive"))
      (node (ref "IC7") (pin "14") (pinfunction "OUT_14") (pintype "output"))
      (node (ref "JP49") (pin "1") (pinfunction "1_1") (pintype "passive"))
      (node (ref "R46") (pin "2") (pinfunction "2_2") (pintype "passive"))
    )
    (net (code "71") (name "Net-(IC9A-+IN)") (class "Default")
      (node (ref "IC9") (pin "3") (pinfunction "+IN_3") (pintype "input"))
      (node (ref "R56") (pin "1") (pinfunction "1_1") (pintype "passive"))
    )
    (net (code "72") (name "Net-(IC9A--IN)") (class "Default")
      (node (ref "IC9") (pin "2") (pinfunction "-IN_2") (pintype "input"))
      (node (ref "R50") (pin "1") (pinfunction "1_1") (pintype "passive"))
      (node (ref "R51") (pin "2") (pinfunction "2_2") (pintype "passive"))
    )
    (net (code "73") (name "Net-(IC9A-OUT)") (class "Default")
      (node (ref "IC9") (pin "1") (pinfunction "OUT_1") (pintype "output"))
      (node (ref "R51") (pin "1") (pinfunction "1_1") (pintype "passive"))
      (node (ref "R85") (pin "2") (pinfunction "2_2") (pintype "passive"))
    )
    (net (code "74") (name "Net-(IC9B--IN)") (class "Default")
      (node (ref "IC9") (pin "6") (pinfunction "-IN_6") (pintype "input"))
      (node (ref "IC9") (pin "7") (pinfunction "OUT_7") (pintype "output"))
    )
    (net (code "75") (name "Net-(IC9C-+IN)") (class "Default")
      (node (ref "IC9") (pin "10") (pinfunction "+IN_10") (pintype "input"))
      (node (ref "R67") (pin "1") (pinfunction "1_1") (pintype "passive"))
    )
    (net (code "76") (name "Net-(IC9C--IN)") (class "Default")
      (node (ref "IC9") (pin "9") (pinfunction "-IN_9") (pintype "input"))
      (node (ref "R69") (pin "2") (pinfunction "2_2") (pintype "passive"))
      (node (ref "R75") (pin "1") (pinfunction "1_1") (pintype "passive"))
    )
    (net (code "77") (name "Net-(IC9C-OUT)") (class "Default")
      (node (ref "IC9") (pin "8") (pinfunction "OUT_8") (pintype "output"))
      (node (ref "R69") (pin "1") (pinfunction "1_1") (pintype "passive"))
      (node (ref "R87") (pin "2") (pinfunction "2_2") (pintype "passive"))
    )
    (net (code "78") (name "Net-(IC9D-+IN)") (class "Default")
      (node (ref "IC9") (pin "12") (pinfunction "+IN_12") (pintype "input"))
      (node (ref "R55") (pin "1") (pinfunction "1_1") (pintype "passive"))
    )
    (net (code "79") (name "Net-(IC9D--IN)") (class "Default")
      (node (ref "IC9") (pin "13") (pinfunction "-IN_13") (pintype "input"))
      (node (ref "R49") (pin "1") (pinfunction "1_1") (pintype "passive"))
      (node (ref "R52") (pin "2") (pinfunction "2_2") (pintype "passive"))
    )
    (net (code "80") (name "Net-(IC9D-OUT)") (class "Default")
      (node (ref "IC9") (pin "14") (pinfunction "OUT_14") (pintype "output"))
      (node (ref "R52") (pin "1") (pinfunction "1_1") (pintype "passive"))
      (node (ref "R86") (pin "2") (pinfunction "2_2") (pintype "passive"))
    )
    (net (code "81") (name "Net-(JP2-Pad1)") (class "Default")
      (node (ref "JP2") (pin "1") (pinfunction "1_1") (pintype "passive"))
      (node (ref "R3") (pin "1") (pinfunction "1_1") (pintype "passive"))
    )
    (net (code "82") (name "Net-(JP2-Pad2)") (class "Default")
      (node (ref "JP2") (pin "2") (pinfunction "2_2") (pintype "passive"))
      (node (ref "R2") (pin "1") (pinfunction "1_1") (pintype "passive"))
    )
    (net (code "83") (name "Net-(JP25-Pad1)") (class "Default")
      (node (ref "JP25") (pin "1") (pinfunction "1_1") (pintype "passive"))
      (node (ref "R64") (pin "2") (pinfunction "2_2") (pintype "passive"))
    )
    (net (code "84") (name "Net-(JP26-Pad1)") (class "Default")
      (node (ref "JP26") (pin "1") (pinfunction "1_1") (pintype "passive"))
      (node (ref "R35") (pin "2") (pinfunction "2_2") (pintype "passive"))
    )
    (net (code "85") (name "Net-(JP27-Pad1)") (class "Default")
      (node (ref "JP27") (pin "1") (pinfunction "1_1") (pintype "passive"))
      (node (ref "R65") (pin "2") (pinfunction "2_2") (pintype "passive"))
    )
    (net (code "86") (name "Net-(JP28-Pad1)") (class "Default")
      (node (ref "JP28") (pin "1") (pinfunction "1_1") (pintype "passive"))
      (node (ref "R34") (pin "2") (pinfunction "2_2") (pintype "passive"))
    )
    (net (code "87") (name "Net-(JP29-Pad1)") (class "Default")
      (node (ref "JP29") (pin "1") (pinfunction "1_1") (pintype "passive"))
      (node (ref "R32") (pin "2") (pinfunction "2_2") (pintype "passive"))
    )
    (net (code "88") (name "Net-(JP31-Pad1)") (class "Default")
      (node (ref "JP31") (pin "1") (pinfunction "1_1") (pintype "passive"))
      (node (ref "R66") (pin "2") (pinfunction "2_2") (pintype "passive"))
    )
    (net (code "89") (name "Net-(JP36-Pad1)") (class "Default")
      (node (ref "JP36") (pin "1") (pinfunction "1_1") (pintype "passive"))
      (node (ref "R33") (pin "2") (pinfunction "2_2") (pintype "passive"))
    )
    (net (code "90") (name "Net-(JP38-Pad1)") (class "Default")
      (node (ref "JP38") (pin "1") (pinfunction "1_1") (pintype "passive"))
      (node (ref "R60") (pin "1") (pinfunction "1_1") (pintype "passive"))
      (node (ref "R62") (pin "1") (pinfunction "1_1") (pintype "passive"))
    )
    (net (code "91") (name "Net-(JP45-Pad1)") (class "Default")
      (node (ref "JP45") (pin "1") (pinfunction "1_1") (pintype "passive"))
      (node (ref "R87") (pin "1") (pinfunction "1_1") (pintype "passive"))
    )
    (net (code "92") (name "Net-(JP46-Pad1)") (class "Default")
      (node (ref "JP46") (pin "1") (pinfunction "1_1") (pintype "passive"))
      (node (ref "R43") (pin "1") (pinfunction "1_1") (pintype "passive"))
      (node (ref "R45") (pin "1") (pinfunction "1_1") (pintype "passive"))
    )
    (net (code "93") (name "Net-(JP48-Pad1)") (class "Default")
      (node (ref "JP48") (pin "1") (pinfunction "1_1") (pintype "passive"))
      (node (ref "R44") (pin "1") (pinfunction "1_1") (pintype "passive"))
      (node (ref "R46") (pin "1") (pinfunction "1_1") (pintype "passive"))
    )
    (net (code "94") (name "Net-(JP51-Pad1)") (class "Default")
      (node (ref "JP51") (pin "1") (pinfunction "1_1") (pintype "passive"))
      (node (ref "R61") (pin "1") (pinfunction "1_1") (pintype "passive"))
      (node (ref "R63") (pin "1") (pinfunction "1_1") (pintype "passive"))
    )
    (net (code "95") (name "Net-(JP52-Pad1)") (class "Default")
      (node (ref "JP52") (pin "1") (pinfunction "1_1") (pintype "passive"))
      (node (ref "R85") (pin "1") (pinfunction "1_1") (pintype "passive"))
    )
    (net (code "96") (name "Net-(JP55-Pad1)") (class "Default")
      (node (ref "JP55") (pin "1") (pinfunction "1_1") (pintype "passive"))
      (node (ref "R86") (pin "1") (pinfunction "1_1") (pintype "passive"))
    )
    (net (code "97") (name "Net-(Q1B-2)") (class "Default")
      (node (ref "C4") (pin "2") (pinfunction "2_2") (pintype "passive"))
      (node (ref "Q1") (pin "3") (pinfunction "2_3") (pintype "passive"))
      (node (ref "R8") (pin "2") (pinfunction "2_2") (pintype "passive"))
    )
    (net (code "98") (name "RESET") (class "Default")
      (node (ref "C7") (pin "1") (pinfunction "1_1") (pintype "passive"))
      (node (ref "IC2") (pin "7") (pinfunction "NRST_7") (pintype "bidirectional"))
      (node (ref "JP1") (pin "4") (pinfunction "4_4") (pintype "passive"))
      (node (ref "R6") (pin "1") (pinfunction "1_1") (pintype "passive"))
    )
    (net (code "99") (name "RX") (class "Default")
      (node (ref "IC2") (pin "43") (pinfunction "PA10/USART1_RX/TIM1_CH3_43") (pintype "bidirectional"))
      (node (ref "R3") (pin "2") (pinfunction "2_2") (pintype "passive"))
    )
    (net (code "100") (name "SWCLK") (class "Default")
      (node (ref "IC2") (pin "49") (pinfunction "PA14/JTCK-SWCLK_49") (pintype "bidirectional"))
      (node (ref "JP1") (pin "1") (pinfunction "1_1") (pintype "passive"))
    )
    (net (code "101") (name "SWDIO") (class "Default")
      (node (ref "IC2") (pin "46") (pinfunction "PA13/JTMS-SWDAT_46") (pintype "bidirectional"))
      (node (ref "JP1") (pin "3") (pinfunction "3_3") (pintype "passive"))
    )
    (net (code "102") (name "SW_T_DV") (class "Default")
      (node (ref "IC2") (pin "30") (pinfunction "PB11/I2C2_SDA/USART3_RX_30") (pintype "bidirectional"))
      (node (ref "JP16") (pin "1") (pinfunction "1_1") (pintype "passive"))
    )
    (net (code "103") (name "SW_T_MODE") (class "Default")
      (node (ref "IC2") (pin "35") (pinfunction "PB14/SPI2_MISO/USART3_RTS/TIM1_CH2N_35") (pintype "bidirectional"))
      (node (ref "JP32") (pin "1") (pinfunction "1_1") (pintype "passive"))
    )
    (net (code "104") (name "SW_T_RANGE") (class "Default")
      (node (ref "IC2") (pin "36") (pinfunction "PB15/SPI2_MOSI/I2S2_SD/TIM1_CH3N_36") (pintype "bidirectional"))
      (node (ref "JP30") (pin "1") (pinfunction "1_1") (pintype "passive"))
    )
    (net (code "105") (name "SW_X_DV") (class "Default")
      (node (ref "IC2") (pin "4") (pinfunction "PC15/OSC_OUT_4") (pintype "bidirectional"))
      (node (ref "JP18") (pin "1") (pinfunction "1_1") (pintype "passive"))
    )
    (net (code "106") (name "SW_X_EXT") (class "Default")
      (node (ref "IC2") (pin "54") (pinfunction "PD2/TIM3-ETR_54") (pintype "bidirectional"))
      (node (ref "JP19") (pin "1") (pinfunction "1_1") (pintype "passive"))
    )
    (net (code "107") (name "SW_X_MODE") (class "Default")
      (node (ref "IC2") (pin "2") (pinfunction "PC13-TAMPER-RTC_2") (pintype "bidirectional"))
      (node (ref "JP33") (pin "1") (pinfunction "1_1") (pintype "passive"))
    )
    (net (code "108") (name "SW_X_RANGE") (class "Default")
      (node (ref "IC2") (pin "58") (pinfunction "PB6/I2C1_SCL/TIM4_CH1/USART1_TX_58") (pintype "bidirectional"))
      (node (ref "JP34") (pin "1") (pinfunction "1_1") (pintype "passive"))
    )
    (net (code "109") (name "TX") (class "Default")
      (node (ref "IC2") (pin "42") (pinfunction "PA9/USART1_TX/TIM1_CH2_42") (pintype "bidirectional"))
      (node (ref "R2") (pin "2") (pinfunction "2_2") (pintype "passive"))
    )
    (net (code "110") (name "T_CLOCK") (class "Default")
      (node (ref "IC2") (pin "40") (pinfunction "PC9/I2S2_CKIN/I2S3_CKIN_40") (pintype "bidirectional"))
      (node (ref "Q2") (pin "C") (pinfunction "C_C") (pintype "passive"))
      (node (ref "R22") (pin "1") (pinfunction "1_1") (pintype "passive"))
    )
    (net (code "111") (name "VCC") (class "Default")
      (node (ref "C11") (pin "+") (pinfunction "+_+") (pintype "passive"))
      (node (ref "C39") (pin "1") (pinfunction "1_1") (pintype "passive"))
      (node (ref "C50") (pin "1") (pinfunction "1_1") (pintype "passive"))
      (node (ref "IC7") (pin "4") (pinfunction "V+_4") (pintype "power_in"))
      (node (ref "IC9") (pin "4") (pinfunction "V+_4") (pintype "power_in"))
      (node (ref "JP58") (pin "1") (pinfunction "1_1") (pintype "passive"))
      (node (ref "L2") (pin "1") (pinfunction "1_1") (pintype "passive"))
    )
    (net (code "112") (name "VEE") (class "Default")
      (node (ref "C22") (pin "-") (pinfunction "-_-") (pintype "passive"))
      (node (ref "C37") (pin "2") (pinfunction "2_2") (pintype "passive"))
      (node (ref "IC7") (pin "11") (pinfunction "V-_11") (pintype "power_in"))
      (node (ref "JP59") (pin "1") (pinfunction "1_1") (pintype "passive"))
      (node (ref "L4") (pin "1") (pinfunction "1_1") (pintype "passive"))
      (node (ref "R68") (pin "1") (pinfunction "1_1") (pintype "passive"))
    )
    (net (code "113") (name "VREF") (class "Default")
      (node (ref "C25") (pin "1") (pinfunction "1_1") (pintype "passive"))
      (node (ref "IC4") (pin "3") (pinfunction "VREFH_3") (pintype "bidirectional"))
      (node (ref "R74") (pin "2") (pinfunction "2_2") (pintype "passive"))
    )
    (net (code "114") (name "VREF_BIAS") (class "Default")
      (node (ref "C51") (pin "1") (pinfunction "1_1") (pintype "passive"))
      (node (ref "IC7") (pin "10") (pinfunction "+IN_10") (pintype "input"))
      (node (ref "IC7") (pin "12") (pinfunction "+IN_12") (pintype "input"))
      (node (ref "IC7") (pin "3") (pinfunction "+IN_3") (pintype "input"))
      (node (ref "IC7") (pin "5") (pinfunction "+IN_5") (pintype "input"))
      (node (ref "R73") (pin "2") (pinfunction "2_2") (pintype "passive"))
      (node (ref "R74") (pin "1") (pinfunction "1_1") (pintype "passive"))
    )
    (net (code "115") (name "X_CLOCK") (class "Default")
      (node (ref "IC2") (pin "41") (pinfunction "PA8/USART1_CK/TIM1_CH1/MCO_41") (pintype "bidirectional"))
      (node (ref "Q3") (pin "C") (pinfunction "C_C") (pintype "passive"))
      (node (ref "R23") (pin "1") (pinfunction "1_1") (pintype "passive"))
    )
    (net (code "116") (name "unconnected-(IC2-PC14{slash}OSC32_IN-Pad3)") (class "Default")
      (node (ref "IC2") (pin "3") (pinfunction "PC14/OSC32_IN_3") (pintype "bidirectional"))
    )
  )
)
